# core_io.net
KiCad netlist of a schematic drawn in EAGLE
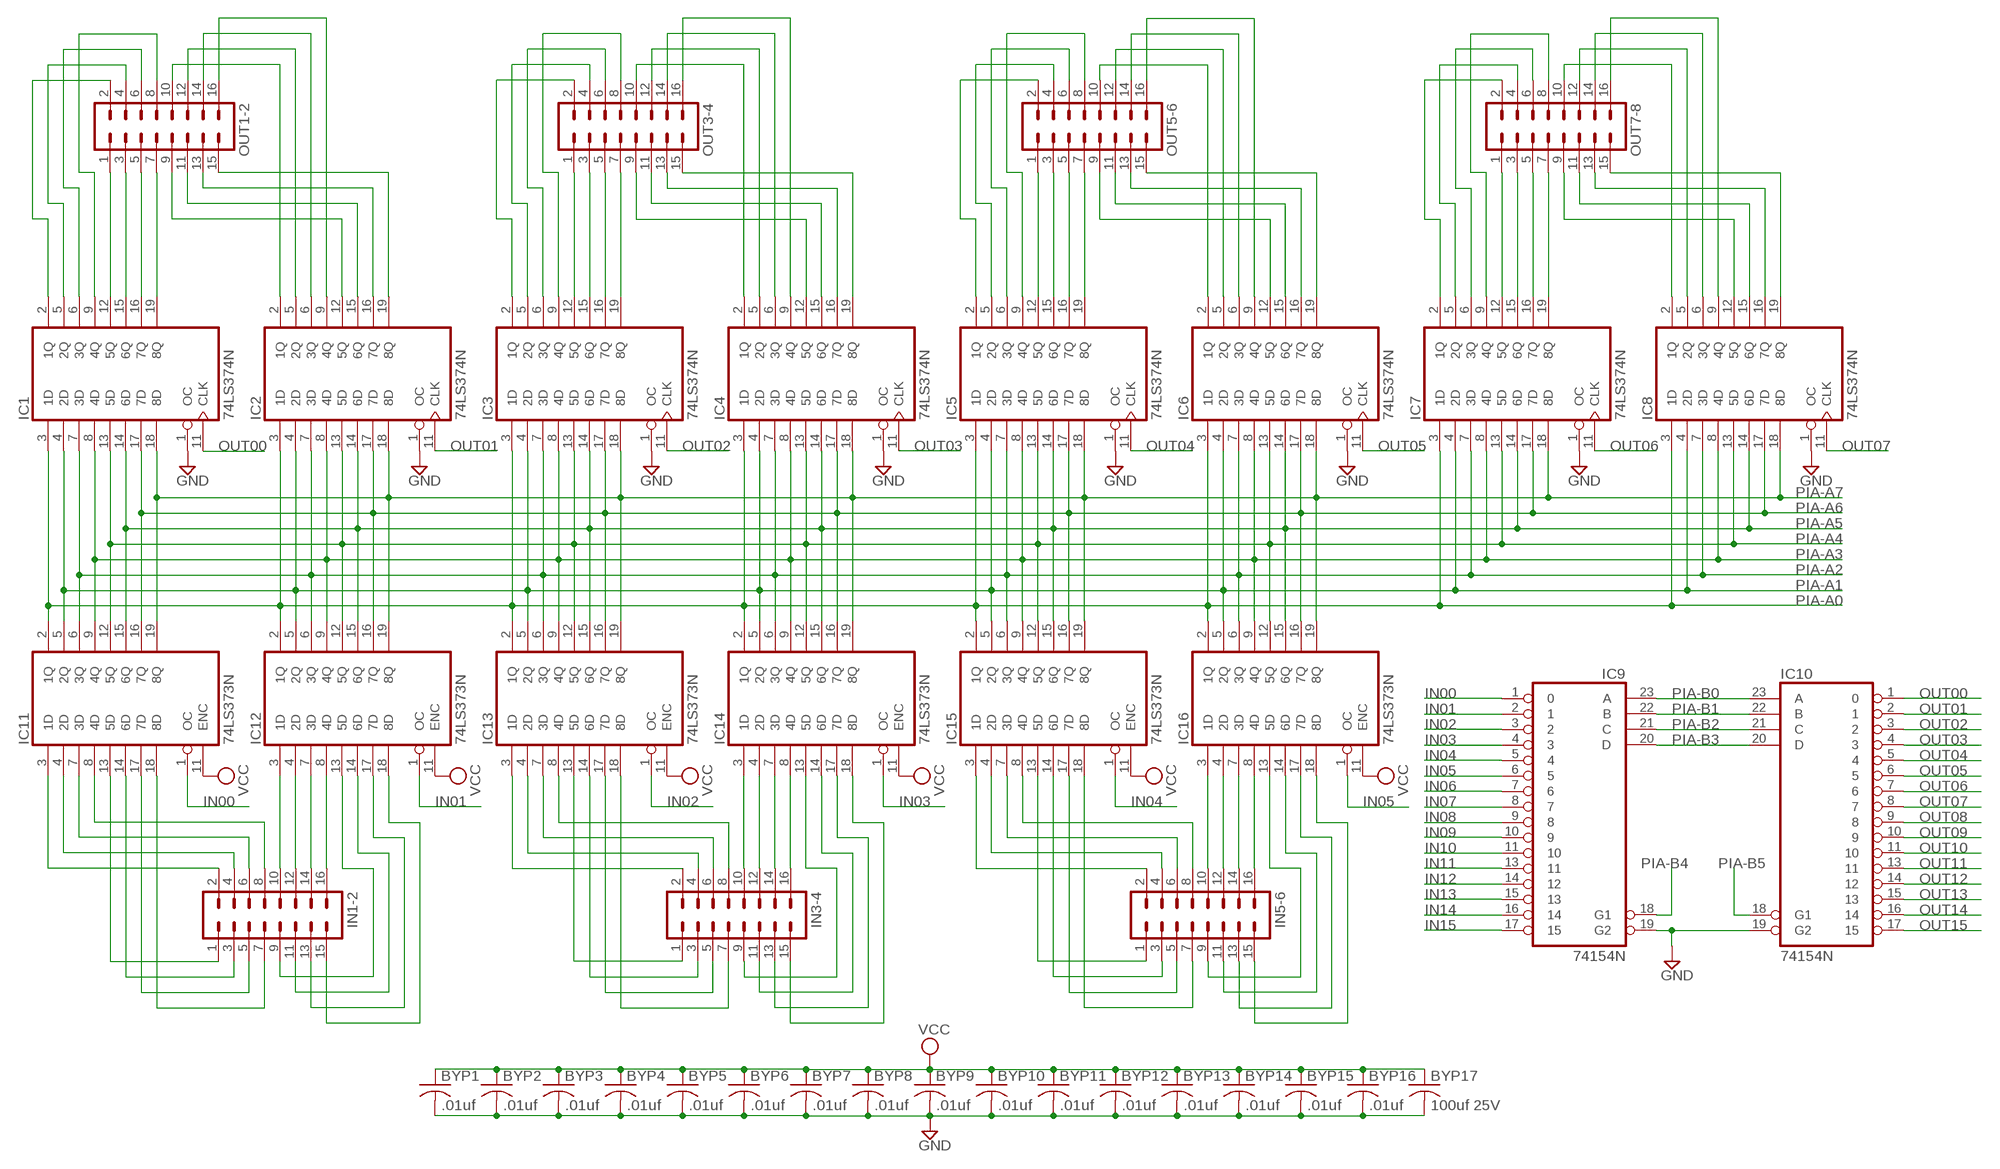
[diagram p0: schematic, sheet 1]
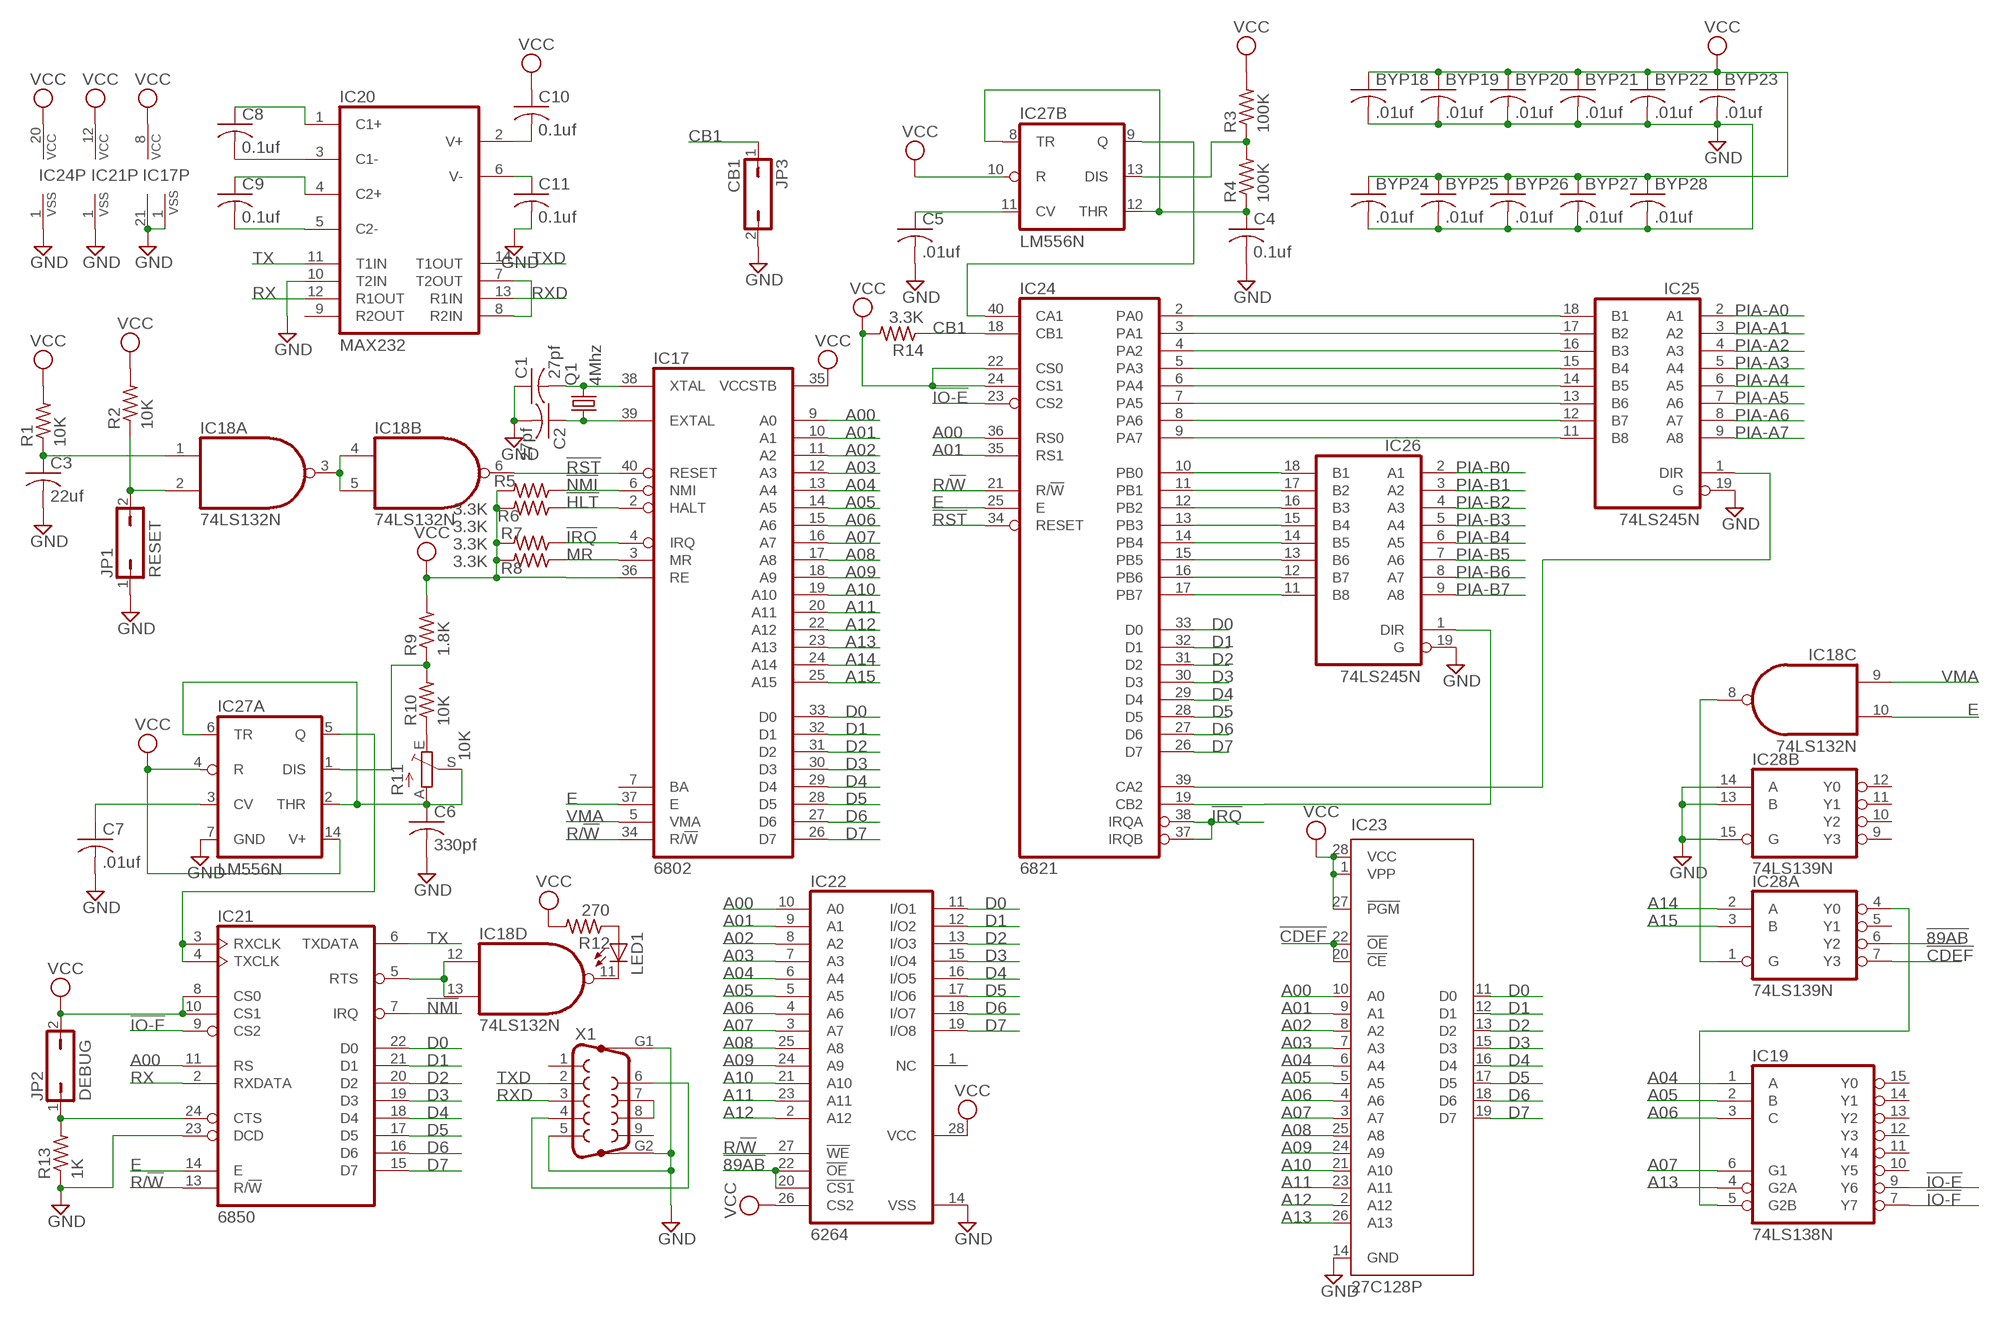
[diagram p1: schematic, sheet 2]
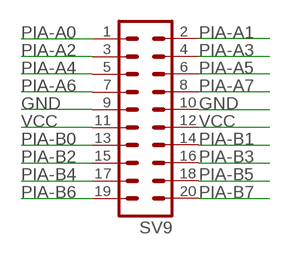
[diagram p2: schematic, sheet 3]

(export (version "E")
  (design (tool "Eeschema 10.0.6"))
  (components
    (comp (ref "SV9")
      (value "MA10-2")
      (footprint "eagle-import:MA10-2")
      (libsource (lib "eagle-import") (part "MA10-2"))
    )
    (comp (ref "BYP1")
      (value ".01uf")
      (footprint "eagle-import:C050-025X075")
      (libsource (lib "eagle-import") (part "C-US050-025X075"))
    )
    (comp (ref "BYP2")
      (value ".01uf")
      (footprint "eagle-import:C050-025X075")
      (libsource (lib "eagle-import") (part "C-US050-025X075"))
    )
    (comp (ref "BYP3")
      (value ".01uf")
      (footprint "eagle-import:C050-025X075")
      (libsource (lib "eagle-import") (part "C-US050-025X075"))
    )
    (comp (ref "BYP4")
      (value ".01uf")
      (footprint "eagle-import:C050-025X075")
      (libsource (lib "eagle-import") (part "C-US050-025X075"))
    )
    (comp (ref "BYP5")
      (value ".01uf")
      (footprint "eagle-import:C050-025X075")
      (libsource (lib "eagle-import") (part "C-US050-025X075"))
    )
    (comp (ref "BYP6")
      (value ".01uf")
      (footprint "eagle-import:C050-025X075")
      (libsource (lib "eagle-import") (part "C-US050-025X075"))
    )
    (comp (ref "BYP7")
      (value ".01uf")
      (footprint "eagle-import:C050-025X075")
      (libsource (lib "eagle-import") (part "C-US050-025X075"))
    )
    (comp (ref "BYP8")
      (value ".01uf")
      (footprint "eagle-import:C050-025X075")
      (libsource (lib "eagle-import") (part "C-US050-025X075"))
    )
    (comp (ref "BYP9")
      (value ".01uf")
      (footprint "eagle-import:C050-025X075")
      (libsource (lib "eagle-import") (part "C-US050-025X075"))
    )
    (comp (ref "BYP10")
      (value ".01uf")
      (footprint "eagle-import:C050-025X075")
      (libsource (lib "eagle-import") (part "C-US050-025X075"))
    )
    (comp (ref "BYP11")
      (value ".01uf")
      (footprint "eagle-import:C050-025X075")
      (libsource (lib "eagle-import") (part "C-US050-025X075"))
    )
    (comp (ref "BYP12")
      (value ".01uf")
      (footprint "eagle-import:C050-025X075")
      (libsource (lib "eagle-import") (part "C-US050-025X075"))
    )
    (comp (ref "BYP13")
      (value ".01uf")
      (footprint "eagle-import:C050-025X075")
      (libsource (lib "eagle-import") (part "C-US050-025X075"))
    )
    (comp (ref "BYP14")
      (value ".01uf")
      (footprint "eagle-import:C050-025X075")
      (libsource (lib "eagle-import") (part "C-US050-025X075"))
    )
    (comp (ref "BYP15")
      (value ".01uf")
      (footprint "eagle-import:C050-025X075")
      (libsource (lib "eagle-import") (part "C-US050-025X075"))
    )
    (comp (ref "BYP16")
      (value ".01uf")
      (footprint "eagle-import:C050-025X075")
      (libsource (lib "eagle-import") (part "C-US050-025X075"))
    )
    (comp (ref "BYP17")
      (value "100uf 25V")
      (footprint "eagle-import:C102-043X133")
      (libsource (lib "eagle-import") (part "C-US102-043X133"))
    )
    (comp (ref "IC1")
      (value "74LS374N")
      (footprint "eagle-import:DIL20")
      (libsource (lib "eagle-import") (part "74374NLS"))
    )
    (comp (ref "IC2")
      (value "74LS374N")
      (footprint "eagle-import:DIL20")
      (libsource (lib "eagle-import") (part "74374NLS"))
    )
    (comp (ref "IC3")
      (value "74LS374N")
      (footprint "eagle-import:DIL20")
      (libsource (lib "eagle-import") (part "74374NLS"))
    )
    (comp (ref "IC4")
      (value "74LS374N")
      (footprint "eagle-import:DIL20")
      (libsource (lib "eagle-import") (part "74374NLS"))
    )
    (comp (ref "IC5")
      (value "74LS374N")
      (footprint "eagle-import:DIL20")
      (libsource (lib "eagle-import") (part "74374NLS"))
    )
    (comp (ref "IC6")
      (value "74LS374N")
      (footprint "eagle-import:DIL20")
      (libsource (lib "eagle-import") (part "74374NLS"))
    )
    (comp (ref "IC7")
      (value "74LS374N")
      (footprint "eagle-import:DIL20")
      (libsource (lib "eagle-import") (part "74374NLS"))
    )
    (comp (ref "IC8")
      (value "74LS374N")
      (footprint "eagle-import:DIL20")
      (libsource (lib "eagle-import") (part "74374NLS"))
    )
    (comp (ref "IC9")
      (value "74154N")
      (footprint "eagle-import:DIL24-6")
      (libsource (lib "eagle-import") (part "74154N"))
    )
    (comp (ref "IC10")
      (value "74154N")
      (footprint "eagle-import:DIL24-6")
      (libsource (lib "eagle-import") (part "74154N"))
    )
    (comp (ref "IC11")
      (value "74LS373N")
      (footprint "eagle-import:DIL20")
      (libsource (lib "eagle-import") (part "74373NLS"))
    )
    (comp (ref "IC12")
      (value "74LS373N")
      (footprint "eagle-import:DIL20")
      (libsource (lib "eagle-import") (part "74373NLS"))
    )
    (comp (ref "IC13")
      (value "74LS373N")
      (footprint "eagle-import:DIL20")
      (libsource (lib "eagle-import") (part "74373NLS"))
    )
    (comp (ref "IC14")
      (value "74LS373N")
      (footprint "eagle-import:DIL20")
      (libsource (lib "eagle-import") (part "74373NLS"))
    )
    (comp (ref "IC15")
      (value "74LS373N")
      (footprint "eagle-import:DIL20")
      (libsource (lib "eagle-import") (part "74373NLS"))
    )
    (comp (ref "IC16")
      (value "74LS373N")
      (footprint "eagle-import:DIL20")
      (libsource (lib "eagle-import") (part "74373NLS"))
    )
    (comp (ref "IN1-2")
      (value "MA08-2")
      (footprint "eagle-import:MA08-2")
      (libsource (lib "eagle-import") (part "MA08-2"))
    )
    (comp (ref "IN3-4")
      (value "MA08-2")
      (footprint "eagle-import:MA08-2")
      (libsource (lib "eagle-import") (part "MA08-2"))
    )
    (comp (ref "IN5-6")
      (value "MA08-2")
      (footprint "eagle-import:MA08-2")
      (libsource (lib "eagle-import") (part "MA08-2"))
    )
    (comp (ref "OUT1-2")
      (value "MA08-2")
      (footprint "eagle-import:MA08-2")
      (libsource (lib "eagle-import") (part "MA08-2"))
    )
    (comp (ref "OUT3-4")
      (value "MA08-2")
      (footprint "eagle-import:MA08-2")
      (libsource (lib "eagle-import") (part "MA08-2"))
    )
    (comp (ref "OUT5-6")
      (value "MA08-2")
      (footprint "eagle-import:MA08-2")
      (libsource (lib "eagle-import") (part "MA08-2"))
    )
    (comp (ref "OUT7-8")
      (value "MA08-2")
      (footprint "eagle-import:MA08-2")
      (libsource (lib "eagle-import") (part "MA08-2"))
    )
    (comp (ref "BYP18")
      (value ".01uf")
      (footprint "eagle-import:C050-025X075")
      (libsource (lib "eagle-import") (part "C-US050-025X075"))
    )
    (comp (ref "BYP19")
      (value ".01uf")
      (footprint "eagle-import:C050-025X075")
      (libsource (lib "eagle-import") (part "C-US050-025X075"))
    )
    (comp (ref "BYP20")
      (value ".01uf")
      (footprint "eagle-import:C050-025X075")
      (libsource (lib "eagle-import") (part "C-US050-025X075"))
    )
    (comp (ref "BYP21")
      (value ".01uf")
      (footprint "eagle-import:C050-025X075")
      (libsource (lib "eagle-import") (part "C-US050-025X075"))
    )
    (comp (ref "BYP22")
      (value ".01uf")
      (footprint "eagle-import:C050-025X075")
      (libsource (lib "eagle-import") (part "C-US050-025X075"))
    )
    (comp (ref "BYP23")
      (value ".01uf")
      (footprint "eagle-import:C050-025X075")
      (libsource (lib "eagle-import") (part "C-US050-025X075"))
    )
    (comp (ref "BYP24")
      (value ".01uf")
      (footprint "eagle-import:C050-025X075")
      (libsource (lib "eagle-import") (part "C-US050-025X075"))
    )
    (comp (ref "BYP25")
      (value ".01uf")
      (footprint "eagle-import:C050-025X075")
      (libsource (lib "eagle-import") (part "C-US050-025X075"))
    )
    (comp (ref "BYP26")
      (value ".01uf")
      (footprint "eagle-import:C050-025X075")
      (libsource (lib "eagle-import") (part "C-US050-025X075"))
    )
    (comp (ref "BYP27")
      (value ".01uf")
      (footprint "eagle-import:C050-025X075")
      (libsource (lib "eagle-import") (part "C-US050-025X075"))
    )
    (comp (ref "BYP28")
      (value ".01uf")
      (footprint "eagle-import:C050-025X075")
      (libsource (lib "eagle-import") (part "C-US050-025X075"))
    )
    (comp (ref "C1")
      (value "27pf")
      (footprint "eagle-import:C050-025X075")
      (libsource (lib "eagle-import") (part "C-US050-025X075"))
    )
    (comp (ref "C2")
      (value "27pf")
      (footprint "eagle-import:C050-025X075")
      (libsource (lib "eagle-import") (part "C-US050-025X075"))
    )
    (comp (ref "C3")
      (value "22uf")
      (footprint "eagle-import:C102-043X133")
      (libsource (lib "eagle-import") (part "C-US102-043X133"))
    )
    (comp (ref "C4")
      (value "0.1uf")
      (footprint "eagle-import:C050-025X075")
      (libsource (lib "eagle-import") (part "C-US050-025X075"))
    )
    (comp (ref "C5")
      (value ".01uf")
      (footprint "eagle-import:C050-025X075")
      (libsource (lib "eagle-import") (part "C-US050-025X075"))
    )
    (comp (ref "C6")
      (value "330pf")
      (footprint "eagle-import:C050-025X075")
      (libsource (lib "eagle-import") (part "C-US050-025X075"))
    )
    (comp (ref "C7")
      (value ".01uf")
      (footprint "eagle-import:C050-025X075")
      (libsource (lib "eagle-import") (part "C-US050-025X075"))
    )
    (comp (ref "C8")
      (value "0.1uf")
      (footprint "eagle-import:C050-025X075")
      (libsource (lib "eagle-import") (part "C-US050-025X075"))
    )
    (comp (ref "C9")
      (value "0.1uf")
      (footprint "eagle-import:C050-025X075")
      (libsource (lib "eagle-import") (part "C-US050-025X075"))
    )
    (comp (ref "C10")
      (value "0.1uf")
      (footprint "eagle-import:C050-025X075")
      (libsource (lib "eagle-import") (part "C-US050-025X075"))
    )
    (comp (ref "C11")
      (value "0.1uf")
      (footprint "eagle-import:C050-025X075")
      (libsource (lib "eagle-import") (part "C-US050-025X075"))
    )
    (comp (ref "IC17")
      (value "6802")
      (footprint "eagle-import:DIL40")
      (libsource (lib "eagle-import") (part "6802"))
    )
    (comp (ref "IC18")
      (value "74LS132N")
      (footprint "eagle-import:DIL14")
      (libsource (lib "eagle-import") (part "7400NLS"))
    )
    (comp (ref "IC19")
      (value "74LS138N")
      (footprint "eagle-import:DIL16")
      (libsource (lib "eagle-import") (part "74138NLS"))
    )
    (comp (ref "IC20")
      (value "MAX232")
      (footprint "eagle-import:DIL16")
      (fields (field (name "MF") "MAXIM") (field (name "MPN") "MAX232ACPE+"))
      (libsource (lib "eagle-import") (part "MAX232"))
    )
    (comp (ref "IC21")
      (value "6850")
      (footprint "eagle-import:DIL24")
      (fields (field (name "MF") "NTE ELECTRONICS") (field (name "MPN") "NTE6850"))
      (libsource (lib "eagle-import") (part "6850"))
    )
    (comp (ref "IC22")
      (value "6264")
      (footprint "eagle-import:DIL28-6")
      (libsource (lib "eagle-import") (part "6264A"))
    )
    (comp (ref "IC23")
      (value "27C128P")
      (footprint "eagle-import:DIL28-6")
      (libsource (lib "eagle-import") (part "27128PC"))
    )
    (comp (ref "IC24")
      (value "6821")
      (footprint "eagle-import:DIL40")
      (fields (field (name "MF") "NTE ELECTRONICS") (field (name "MPN") "NTE6821"))
      (libsource (lib "eagle-import") (part "6821"))
    )
    (comp (ref "IC25")
      (value "74LS245N")
      (footprint "eagle-import:DIL20")
      (libsource (lib "eagle-import") (part "74245NLS"))
    )
    (comp (ref "IC26")
      (value "74LS245N")
      (footprint "eagle-import:DIL20")
      (libsource (lib "eagle-import") (part "74245NLS"))
    )
    (comp (ref "IC27")
      (value "LM556N")
      (footprint "eagle-import:DIL14")
      (libsource (lib "eagle-import") (part "556NLM"))
    )
    (comp (ref "IC28")
      (value "74LS139N")
      (footprint "eagle-import:DIL16")
      (libsource (lib "eagle-import") (part "74139NLS"))
    )
    (comp (ref "JP1")
      (value "RESET")
      (footprint "eagle-import:JP1")
      (libsource (lib "eagle-import") (part "JP1Q"))
    )
    (comp (ref "JP2")
      (value "DEBUG")
      (footprint "eagle-import:JP1")
      (libsource (lib "eagle-import") (part "JP1Q"))
    )
    (comp (ref "JP3")
      (value "CB1")
      (footprint "eagle-import:JP1")
      (libsource (lib "eagle-import") (part "JP1Q"))
    )
    (comp (ref "LED1")
      (value "LED3MM")
      (footprint "eagle-import:LED3MM")
      (libsource (lib "eagle-import") (part "LED3MM"))
    )
    (comp (ref "Q1")
      (value "4Mhz")
      (footprint "eagle-import:HC18U-V")
      (libsource (lib "eagle-import") (part "CRYSTALHC18U-V"))
    )
    (comp (ref "R1")
      (value "10K")
      (footprint "eagle-import:0207_7")
      (libsource (lib "eagle-import") (part "R-US_0207/7"))
    )
    (comp (ref "R2")
      (value "10K")
      (footprint "eagle-import:0207_7")
      (libsource (lib "eagle-import") (part "R-US_0207/7"))
    )
    (comp (ref "R3")
      (value "100K")
      (footprint "eagle-import:0207_7")
      (libsource (lib "eagle-import") (part "R-US_0207/7"))
    )
    (comp (ref "R4")
      (value "100K")
      (footprint "eagle-import:0207_7")
      (libsource (lib "eagle-import") (part "R-US_0207/7"))
    )
    (comp (ref "R5")
      (value "3.3K")
      (footprint "eagle-import:0207_7")
      (libsource (lib "eagle-import") (part "R-US_0207/7"))
    )
    (comp (ref "R6")
      (value "3.3K")
      (footprint "eagle-import:0207_7")
      (libsource (lib "eagle-import") (part "R-US_0207/7"))
    )
    (comp (ref "R7")
      (value "3.3K")
      (footprint "eagle-import:0207_7")
      (libsource (lib "eagle-import") (part "R-US_0207/7"))
    )
    (comp (ref "R8")
      (value "3.3K")
      (footprint "eagle-import:0207_7")
      (libsource (lib "eagle-import") (part "R-US_0207/7"))
    )
    (comp (ref "R9")
      (value "1.8K")
      (footprint "eagle-import:0207_7")
      (libsource (lib "eagle-import") (part "R-US_0207/7"))
    )
    (comp (ref "R10")
      (value "10K")
      (footprint "eagle-import:0207_7")
      (libsource (lib "eagle-import") (part "R-US_0207/7"))
    )
    (comp (ref "R11")
      (value "10K")
      (footprint "eagle-import:SP19L")
      (libsource (lib "eagle-import") (part "TRIM_EU-B90P"))
    )
    (comp (ref "R12")
      (value "270")
      (footprint "eagle-import:0207_7")
      (libsource (lib "eagle-import") (part "R-US_0207/7"))
    )
    (comp (ref "R13")
      (value "1K")
      (footprint "eagle-import:0207_7")
      (libsource (lib "eagle-import") (part "R-US_0207/7"))
    )
    (comp (ref "R14")
      (value "3.3K")
      (footprint "eagle-import:0207_7")
      (libsource (lib "eagle-import") (part "R-US_0207/7"))
    )
    (comp (ref "X1")
      (value "F09HP")
      (footprint "eagle-import:F09HP")
      (libsource (lib "eagle-import") (part "F09HP"))
    )
  )
  (nets
    (net (code "1") (name "A00") (class "Default")
      (node (ref "IC17") (pin "9") (pinfunction "A0_9") (pintype "output"))
      (node (ref "IC21") (pin "11") (pinfunction "RS_11") (pintype "input"))
      (node (ref "IC22") (pin "10") (pinfunction "A0_10") (pintype "input"))
      (node (ref "IC23") (pin "10") (pinfunction "A0_10") (pintype "input"))
      (node (ref "IC24") (pin "36") (pinfunction "RS0_36") (pintype "input"))
    )
    (net (code "2") (name "A01") (class "Default")
      (node (ref "IC17") (pin "10") (pinfunction "A1_10") (pintype "output"))
      (node (ref "IC22") (pin "9") (pinfunction "A1_9") (pintype "input"))
      (node (ref "IC23") (pin "9") (pinfunction "A1_9") (pintype "input"))
      (node (ref "IC24") (pin "35") (pinfunction "RS1_35") (pintype "input"))
    )
    (net (code "3") (name "A02") (class "Default")
      (node (ref "IC17") (pin "11") (pinfunction "A2_11") (pintype "output"))
      (node (ref "IC22") (pin "8") (pinfunction "A2_8") (pintype "input"))
      (node (ref "IC23") (pin "8") (pinfunction "A2_8") (pintype "input"))
    )
    (net (code "4") (name "A03") (class "Default")
      (node (ref "IC17") (pin "12") (pinfunction "A3_12") (pintype "output"))
      (node (ref "IC22") (pin "7") (pinfunction "A3_7") (pintype "input"))
      (node (ref "IC23") (pin "7") (pinfunction "A3_7") (pintype "input"))
    )
    (net (code "5") (name "A04") (class "Default")
      (node (ref "IC17") (pin "13") (pinfunction "A4_13") (pintype "output"))
      (node (ref "IC19") (pin "1") (pinfunction "A_1") (pintype "input"))
      (node (ref "IC22") (pin "6") (pinfunction "A4_6") (pintype "input"))
      (node (ref "IC23") (pin "6") (pinfunction "A4_6") (pintype "input"))
    )
    (net (code "6") (name "A05") (class "Default")
      (node (ref "IC17") (pin "14") (pinfunction "A5_14") (pintype "output"))
      (node (ref "IC19") (pin "2") (pinfunction "B_2") (pintype "input"))
      (node (ref "IC22") (pin "5") (pinfunction "A5_5") (pintype "input"))
      (node (ref "IC23") (pin "5") (pinfunction "A5_5") (pintype "input"))
    )
    (net (code "7") (name "A06") (class "Default")
      (node (ref "IC17") (pin "15") (pinfunction "A6_15") (pintype "output"))
      (node (ref "IC19") (pin "3") (pinfunction "C_3") (pintype "input"))
      (node (ref "IC22") (pin "4") (pinfunction "A6_4") (pintype "input"))
      (node (ref "IC23") (pin "4") (pinfunction "A6_4") (pintype "input"))
    )
    (net (code "8") (name "A07") (class "Default")
      (node (ref "IC17") (pin "16") (pinfunction "A7_16") (pintype "output"))
      (node (ref "IC19") (pin "6") (pinfunction "G1_6") (pintype "input"))
      (node (ref "IC22") (pin "3") (pinfunction "A7_3") (pintype "input"))
      (node (ref "IC23") (pin "3") (pinfunction "A7_3") (pintype "input"))
    )
    (net (code "9") (name "A08") (class "Default")
      (node (ref "IC17") (pin "17") (pinfunction "A8_17") (pintype "output"))
      (node (ref "IC22") (pin "25") (pinfunction "A8_25") (pintype "input"))
      (node (ref "IC23") (pin "25") (pinfunction "A8_25") (pintype "input"))
    )
    (net (code "10") (name "A09") (class "Default")
      (node (ref "IC17") (pin "18") (pinfunction "A9_18") (pintype "output"))
      (node (ref "IC22") (pin "24") (pinfunction "A9_24") (pintype "input"))
      (node (ref "IC23") (pin "24") (pinfunction "A9_24") (pintype "input"))
    )
    (net (code "11") (name "A10") (class "Default")
      (node (ref "IC17") (pin "19") (pinfunction "A10_19") (pintype "output"))
      (node (ref "IC22") (pin "21") (pinfunction "A10_21") (pintype "input"))
      (node (ref "IC23") (pin "21") (pinfunction "A10_21") (pintype "input"))
    )
    (net (code "12") (name "A11") (class "Default")
      (node (ref "IC17") (pin "20") (pinfunction "A11_20") (pintype "output"))
      (node (ref "IC22") (pin "23") (pinfunction "A11_23") (pintype "input"))
      (node (ref "IC23") (pin "23") (pinfunction "A11_23") (pintype "input"))
    )
    (net (code "13") (name "A12") (class "Default")
      (node (ref "IC17") (pin "22") (pinfunction "A12_22") (pintype "output"))
      (node (ref "IC22") (pin "2") (pinfunction "A12_2") (pintype "input"))
      (node (ref "IC23") (pin "2") (pinfunction "A12_2") (pintype "input"))
    )
    (net (code "14") (name "A13") (class "Default")
      (node (ref "IC17") (pin "23") (pinfunction "A13_23") (pintype "output"))
      (node (ref "IC19") (pin "4") (pinfunction "G2A_4") (pintype "input"))
      (node (ref "IC23") (pin "26") (pinfunction "A13_26") (pintype "input"))
    )
    (net (code "15") (name "A14") (class "Default")
      (node (ref "IC17") (pin "24") (pinfunction "A14_24") (pintype "output"))
      (node (ref "IC28") (pin "2") (pinfunction "A_2") (pintype "input"))
    )
    (net (code "16") (name "A15") (class "Default")
      (node (ref "IC17") (pin "25") (pinfunction "A15_25") (pintype "output"))
      (node (ref "IC28") (pin "3") (pinfunction "B_3") (pintype "input"))
    )
    (net (code "17") (name "CB1") (class "Default")
      (node (ref "IC24") (pin "18") (pinfunction "CB1_18") (pintype "input"))
      (node (ref "JP3") (pin "1") (pinfunction "1_1") (pintype "passive"))
      (node (ref "R14") (pin "1") (pinfunction "1_1") (pintype "passive"))
    )
    (net (code "18") (name "D0") (class "Default")
      (node (ref "IC17") (pin "33") (pinfunction "D0_33") (pintype "bidirectional"))
      (node (ref "IC21") (pin "22") (pinfunction "D0_22") (pintype "bidirectional"))
      (node (ref "IC22") (pin "11") (pinfunction "I/O1_11") (pintype "bidirectional"))
      (node (ref "IC23") (pin "11") (pinfunction "D0_11") (pintype "tri_state"))
      (node (ref "IC24") (pin "33") (pinfunction "D0_33") (pintype "bidirectional"))
    )
    (net (code "19") (name "D1") (class "Default")
      (node (ref "IC17") (pin "32") (pinfunction "D1_32") (pintype "bidirectional"))
      (node (ref "IC21") (pin "21") (pinfunction "D1_21") (pintype "bidirectional"))
      (node (ref "IC22") (pin "12") (pinfunction "I/O2_12") (pintype "bidirectional"))
      (node (ref "IC23") (pin "12") (pinfunction "D1_12") (pintype "tri_state"))
      (node (ref "IC24") (pin "32") (pinfunction "D1_32") (pintype "bidirectional"))
    )
    (net (code "20") (name "D2") (class "Default")
      (node (ref "IC17") (pin "31") (pinfunction "D2_31") (pintype "bidirectional"))
      (node (ref "IC21") (pin "20") (pinfunction "D2_20") (pintype "bidirectional"))
      (node (ref "IC22") (pin "13") (pinfunction "I/O3_13") (pintype "bidirectional"))
      (node (ref "IC23") (pin "13") (pinfunction "D2_13") (pintype "tri_state"))
      (node (ref "IC24") (pin "31") (pinfunction "D2_31") (pintype "bidirectional"))
    )
    (net (code "21") (name "D3") (class "Default")
      (node (ref "IC17") (pin "30") (pinfunction "D3_30") (pintype "bidirectional"))
      (node (ref "IC21") (pin "19") (pinfunction "D3_19") (pintype "bidirectional"))
      (node (ref "IC22") (pin "15") (pinfunction "I/O4_15") (pintype "bidirectional"))
      (node (ref "IC23") (pin "15") (pinfunction "D3_15") (pintype "tri_state"))
      (node (ref "IC24") (pin "30") (pinfunction "D3_30") (pintype "bidirectional"))
    )
    (net (code "22") (name "D4") (class "Default")
      (node (ref "IC17") (pin "29") (pinfunction "D4_29") (pintype "bidirectional"))
      (node (ref "IC21") (pin "18") (pinfunction "D4_18") (pintype "bidirectional"))
      (node (ref "IC22") (pin "16") (pinfunction "I/O5_16") (pintype "bidirectional"))
      (node (ref "IC23") (pin "16") (pinfunction "D4_16") (pintype "tri_state"))
      (node (ref "IC24") (pin "29") (pinfunction "D4_29") (pintype "bidirectional"))
    )
    (net (code "23") (name "D5") (class "Default")
      (node (ref "IC17") (pin "28") (pinfunction "D5_28") (pintype "bidirectional"))
      (node (ref "IC21") (pin "17") (pinfunction "D5_17") (pintype "bidirectional"))
      (node (ref "IC22") (pin "17") (pinfunction "I/O6_17") (pintype "bidirectional"))
      (node (ref "IC23") (pin "17") (pinfunction "D5_17") (pintype "tri_state"))
      (node (ref "IC24") (pin "28") (pinfunction "D5_28") (pintype "bidirectional"))
    )
    (net (code "24") (name "D6") (class "Default")
      (node (ref "IC17") (pin "27") (pinfunction "D6_27") (pintype "bidirectional"))
      (node (ref "IC21") (pin "16") (pinfunction "D6_16") (pintype "bidirectional"))
      (node (ref "IC22") (pin "18") (pinfunction "I/O7_18") (pintype "bidirectional"))
      (node (ref "IC23") (pin "18") (pinfunction "D6_18") (pintype "tri_state"))
      (node (ref "IC24") (pin "27") (pinfunction "D6_27") (pintype "bidirectional"))
    )
    (net (code "25") (name "D7") (class "Default")
      (node (ref "IC17") (pin "26") (pinfunction "D7_26") (pintype "bidirectional"))
      (node (ref "IC21") (pin "15") (pinfunction "D7_15") (pintype "bidirectional"))
      (node (ref "IC22") (pin "19") (pinfunction "I/O8_19") (pintype "bidirectional"))
      (node (ref "IC23") (pin "19") (pinfunction "D7_19") (pintype "tri_state"))
      (node (ref "IC24") (pin "26") (pinfunction "D7_26") (pintype "bidirectional"))
    )
    (net (code "26") (name "E") (class "Default")
      (node (ref "IC17") (pin "37") (pinfunction "E_37") (pintype "output"))
      (node (ref "IC18") (pin "10") (pinfunction "I1_10") (pintype "input"))
      (node (ref "IC21") (pin "14") (pinfunction "E_14") (pintype "input"))
      (node (ref "IC24") (pin "25") (pinfunction "E_25") (pintype "input"))
    )
    (net (code "27") (name "GND") (class "Default")
      (node (ref "BYP1") (pin "2") (pinfunction "2_2") (pintype "passive"))
      (node (ref "BYP10") (pin "2") (pinfunction "2_2") (pintype "passive"))
      (node (ref "BYP11") (pin "2") (pinfunction "2_2") (pintype "passive"))
      (node (ref "BYP12") (pin "2") (pinfunction "2_2") (pintype "passive"))
      (node (ref "BYP13") (pin "2") (pinfunction "2_2") (pintype "passive"))
      (node (ref "BYP14") (pin "2") (pinfunction "2_2") (pintype "passive"))
      (node (ref "BYP15") (pin "2") (pinfunction "2_2") (pintype "passive"))
      (node (ref "BYP16") (pin "2") (pinfunction "2_2") (pintype "passive"))
      (node (ref "BYP17") (pin "2") (pinfunction "2_2") (pintype "passive"))
      (node (ref "BYP18") (pin "2") (pinfunction "2_2") (pintype "passive"))
      (node (ref "BYP19") (pin "2") (pinfunction "2_2") (pintype "passive"))
      (node (ref "BYP2") (pin "2") (pinfunction "2_2") (pintype "passive"))
      (node (ref "BYP20") (pin "2") (pinfunction "2_2") (pintype "passive"))
      (node (ref "BYP21") (pin "2") (pinfunction "2_2") (pintype "passive"))
      (node (ref "BYP22") (pin "2") (pinfunction "2_2") (pintype "passive"))
      (node (ref "BYP23") (pin "2") (pinfunction "2_2") (pintype "passive"))
      (node (ref "BYP24") (pin "2") (pinfunction "2_2") (pintype "passive"))
      (node (ref "BYP25") (pin "2") (pinfunction "2_2") (pintype "passive"))
      (node (ref "BYP26") (pin "2") (pinfunction "2_2") (pintype "passive"))
      (node (ref "BYP27") (pin "2") (pinfunction "2_2") (pintype "passive"))
      (node (ref "BYP28") (pin "2") (pinfunction "2_2") (pintype "passive"))
      (node (ref "BYP3") (pin "2") (pinfunction "2_2") (pintype "passive"))
      (node (ref "BYP4") (pin "2") (pinfunction "2_2") (pintype "passive"))
      (node (ref "BYP5") (pin "2") (pinfunction "2_2") (pintype "passive"))
      (node (ref "BYP6") (pin "2") (pinfunction "2_2") (pintype "passive"))
      (node (ref "BYP7") (pin "2") (pinfunction "2_2") (pintype "passive"))
      (node (ref "BYP8") (pin "2") (pinfunction "2_2") (pintype "passive"))
      (node (ref "BYP9") (pin "2") (pinfunction "2_2") (pintype "passive"))
      (node (ref "C1") (pin "1") (pinfunction "1_1") (pintype "passive"))
      (node (ref "C11") (pin "2") (pinfunction "2_2") (pintype "passive"))
      (node (ref "C2") (pin "2") (pinfunction "2_2") (pintype "passive"))
      (node (ref "C3") (pin "2") (pinfunction "2_2") (pintype "passive"))
      (node (ref "C4") (pin "2") (pinfunction "2_2") (pintype "passive"))
      (node (ref "C5") (pin "2") (pinfunction "2_2") (pintype "passive"))
      (node (ref "C6") (pin "2") (pinfunction "2_2") (pintype "passive"))
      (node (ref "C7") (pin "2") (pinfunction "2_2") (pintype "passive"))
      (node (ref "IC1") (pin "1") (pinfunction "OC_1") (pintype "input"))
      (node (ref "IC10") (pin "19") (pinfunction "G2_19") (pintype "input"))
      (node (ref "IC17") (pin "1") (pinfunction "VSS_1") (pintype "power_in"))
      (node (ref "IC17") (pin "21") (pinfunction "VSS_21") (pintype "power_in"))
      (node (ref "IC2") (pin "1") (pinfunction "OC_1") (pintype "input"))
      (node (ref "IC20") (pin "10") (pinfunction "T2IN_10") (pintype "input"))
      (node (ref "IC21") (pin "1") (pinfunction "VSS_1") (pintype "power_in"))
      (node (ref "IC21") (pin "23") (pinfunction "DCD_23") (pintype "input"))
      (node (ref "IC22") (pin "14") (pinfunction "VSS_14") (pintype "power_in"))
      (node (ref "IC23") (pin "14") (pinfunction "GND_14") (pintype "power_in"))
      (node (ref "IC24") (pin "1") (pinfunction "VSS_1") (pintype "power_in"))
      (node (ref "IC25") (pin "19") (pinfunction "G_19") (pintype "input"))
      (node (ref "IC26") (pin "19") (pinfunction "G_19") (pintype "input"))
      (node (ref "IC27") (pin "7") (pinfunction "GND_7") (pintype "power_in"))
      (node (ref "IC28") (pin "13") (pinfunction "B_13") (pintype "input"))
      (node (ref "IC28") (pin "14") (pinfunction "A_14") (pintype "input"))
      (node (ref "IC28") (pin "15") (pinfunction "G_15") (pintype "input"))
      (node (ref "IC3") (pin "1") (pinfunction "OC_1") (pintype "input"))
      (node (ref "IC4") (pin "1") (pinfunction "OC_1") (pintype "input"))
      (node (ref "IC5") (pin "1") (pinfunction "OC_1") (pintype "input"))
      (node (ref "IC6") (pin "1") (pinfunction "OC_1") (pintype "input"))
      (node (ref "IC7") (pin "1") (pinfunction "OC_1") (pintype "input"))
      (node (ref "IC8") (pin "1") (pinfunction "OC_1") (pintype "input"))
      (node (ref "IC9") (pin "19") (pinfunction "G2_19") (pintype "input"))
      (node (ref "JP1") (pin "1") (pinfunction "1_1") (pintype "passive"))
      (node (ref "JP3") (pin "2") (pinfunction "2_2") (pintype "passive"))
      (node (ref "R13") (pin "1") (pinfunction "1_1") (pintype "passive"))
      (node (ref "SV9") (pin "10") (pinfunction "10_10") (pintype "passive"))
      (node (ref "SV9") (pin "9") (pinfunction "9_9") (pintype "passive"))
      (node (ref "X1") (pin "5") (pinfunction "5_5") (pintype "passive"))
      (node (ref "X1") (pin "G1") (pinfunction "G1_G1") (pintype "passive"))
      (node (ref "X1") (pin "G2") (pinfunction "G2_G2") (pintype "passive"))
    )
    (net (code "28") (name "IN00") (class "Default")
      (node (ref "IC11") (pin "1") (pinfunction "OC_1") (pintype "input"))
      (node (ref "IC9") (pin "1") (pinfunction "0_1") (pintype "output"))
    )
    (net (code "29") (name "IN01") (class "Default")
      (node (ref "IC12") (pin "1") (pinfunction "OC_1") (pintype "input"))
      (node (ref "IC9") (pin "2") (pinfunction "1_2") (pintype "output"))
    )
    (net (code "30") (name "IN02") (class "Default")
      (node (ref "IC13") (pin "1") (pinfunction "OC_1") (pintype "input"))
      (node (ref "IC9") (pin "3") (pinfunction "2_3") (pintype "output"))
    )
    (net (code "31") (name "IN03") (class "Default")
      (node (ref "IC14") (pin "1") (pinfunction "OC_1") (pintype "input"))
      (node (ref "IC9") (pin "4") (pinfunction "3_4") (pintype "output"))
    )
    (net (code "32") (name "IN04") (class "Default")
      (node (ref "IC15") (pin "1") (pinfunction "OC_1") (pintype "input"))
      (node (ref "IC9") (pin "5") (pinfunction "4_5") (pintype "output"))
    )
    (net (code "33") (name "IN05") (class "Default")
      (node (ref "IC16") (pin "1") (pinfunction "OC_1") (pintype "input"))
      (node (ref "IC9") (pin "6") (pinfunction "5_6") (pintype "output"))
    )
    (net (code "34") (name "IN06") (class "Default")
      (node (ref "IC9") (pin "7") (pinfunction "6_7") (pintype "output"))
    )
    (net (code "35") (name "IN07") (class "Default")
      (node (ref "IC9") (pin "8") (pinfunction "7_8") (pintype "output"))
    )
    (net (code "36") (name "IN08") (class "Default")
      (node (ref "IC9") (pin "9") (pinfunction "8_9") (pintype "output"))
    )
    (net (code "37") (name "IN09") (class "Default")
      (node (ref "IC9") (pin "10") (pinfunction "9_10") (pintype "output"))
    )
    (net (code "38") (name "IN10") (class "Default")
      (node (ref "IC9") (pin "11") (pinfunction "10_11") (pintype "output"))
    )
    (net (code "39") (name "IN11") (class "Default")
      (node (ref "IC9") (pin "13") (pinfunction "11_13") (pintype "output"))
    )
    (net (code "40") (name "IN12") (class "Default")
      (node (ref "IC9") (pin "14") (pinfunction "12_14") (pintype "output"))
    )
    (net (code "41") (name "IN13") (class "Default")
      (node (ref "IC9") (pin "15") (pinfunction "13_15") (pintype "output"))
    )
    (net (code "42") (name "IN14") (class "Default")
      (node (ref "IC9") (pin "16") (pinfunction "14_16") (pintype "output"))
    )
    (net (code "43") (name "IN15") (class "Default")
      (node (ref "IC9") (pin "17") (pinfunction "15_17") (pintype "output"))
    )
    (net (code "44") (name "MR") (class "Default")
      (node (ref "IC17") (pin "3") (pinfunction "MR_3") (pintype "input"))
      (node (ref "R8") (pin "1") (pinfunction "1_1") (pintype "passive"))
    )
    (net (code "45") (name "Net-(IC1A-1Q)") (class "Default")
      (node (ref "IC1") (pin "2") (pinfunction "1Q_2") (pintype "tri_state"))
      (node (ref "OUT1-2") (pin "2") (pinfunction "2_2") (pintype "passive"))
    )
    (net (code "46") (name "Net-(IC1A-2Q)") (class "Default")
      (node (ref "IC1") (pin "5") (pinfunction "2Q_5") (pintype "tri_state"))
      (node (ref "OUT1-2") (pin "4") (pinfunction "4_4") (pintype "passive"))
    )
    (net (code "47") (name "Net-(IC1A-3Q)") (class "Default")
      (node (ref "IC1") (pin "6") (pinfunction "3Q_6") (pintype "tri_state"))
      (node (ref "OUT1-2") (pin "6") (pinfunction "6_6") (pintype "passive"))
    )
    (net (code "48") (name "Net-(IC1A-4Q)") (class "Default")
      (node (ref "IC1") (pin "9") (pinfunction "4Q_9") (pintype "tri_state"))
      (node (ref "OUT1-2") (pin "8") (pinfunction "8_8") (pintype "passive"))
    )
    (net (code "49") (name "Net-(IC1A-5Q)") (class "Default")
      (node (ref "IC1") (pin "12") (pinfunction "5Q_12") (pintype "tri_state"))
      (node (ref "OUT1-2") (pin "1") (pinfunction "1_1") (pintype "passive"))
    )
    (net (code "50") (name "Net-(IC1A-6Q)") (class "Default")
      (node (ref "IC1") (pin "15") (pinfunction "6Q_15") (pintype "tri_state"))
      (node (ref "OUT1-2") (pin "3") (pinfunction "3_3") (pintype "passive"))
    )
    (net (code "51") (name "Net-(IC1A-7Q)") (class "Default")
      (node (ref "IC1") (pin "16") (pinfunction "7Q_16") (pintype "tri_state"))
      (node (ref "OUT1-2") (pin "5") (pinfunction "5_5") (pintype "passive"))
    )
    (net (code "52") (name "Net-(IC1A-8Q)") (class "Default")
      (node (ref "IC1") (pin "19") (pinfunction "8Q_19") (pintype "tri_state"))
      (node (ref "OUT1-2") (pin "7") (pinfunction "7_7") (pintype "passive"))
    )
    (net (code "53") (name "Net-(IC2A-1Q)") (class "Default")
      (node (ref "IC2") (pin "2") (pinfunction "1Q_2") (pintype "tri_state"))
      (node (ref "OUT1-2") (pin "10") (pinfunction "10_10") (pintype "passive"))
    )
    (net (code "54") (name "Net-(IC2A-2Q)") (class "Default")
      (node (ref "IC2") (pin "5") (pinfunction "2Q_5") (pintype "tri_state"))
      (node (ref "OUT1-2") (pin "12") (pinfunction "12_12") (pintype "passive"))
    )
    (net (code "55") (name "Net-(IC2A-3Q)") (class "Default")
      (node (ref "IC2") (pin "6") (pinfunction "3Q_6") (pintype "tri_state"))
      (node (ref "OUT1-2") (pin "14") (pinfunction "14_14") (pintype "passive"))
    )
    (net (code "56") (name "Net-(IC2A-4Q)") (class "Default")
      (node (ref "IC2") (pin "9") (pinfunction "4Q_9") (pintype "tri_state"))
      (node (ref "OUT1-2") (pin "16") (pinfunction "16_16") (pintype "passive"))
    )
    (net (code "57") (name "Net-(IC2A-5Q)") (class "Default")
      (node (ref "IC2") (pin "12") (pinfunction "5Q_12") (pintype "tri_state"))
      (node (ref "OUT1-2") (pin "9") (pinfunction "9_9") (pintype "passive"))
    )
    (net (code "58") (name "Net-(IC2A-6Q)") (class "Default")
      (node (ref "IC2") (pin "15") (pinfunction "6Q_15") (pintype "tri_state"))
      (node (ref "OUT1-2") (pin "11") (pinfunction "11_11") (pintype "passive"))
    )
    (net (code "59") (name "Net-(IC2A-7Q)") (class "Default")
      (node (ref "IC2") (pin "16") (pinfunction "7Q_16") (pintype "tri_state"))
      (node (ref "OUT1-2") (pin "13") (pinfunction "13_13") (pintype "passive"))
    )
    (net (code "60") (name "Net-(IC2A-8Q)") (class "Default")
      (node (ref "IC2") (pin "19") (pinfunction "8Q_19") (pintype "tri_state"))
      (node (ref "OUT1-2") (pin "15") (pinfunction "15_15") (pintype "passive"))
    )
    (net (code "61") (name "Net-(IC3A-1Q)") (class "Default")
      (node (ref "IC3") (pin "2") (pinfunction "1Q_2") (pintype "tri_state"))
      (node (ref "OUT3-4") (pin "2") (pinfunction "2_2") (pintype "passive"))
    )
    (net (code "62") (name "Net-(IC3A-2Q)") (class "Default")
      (node (ref "IC3") (pin "5") (pinfunction "2Q_5") (pintype "tri_state"))
      (node (ref "OUT3-4") (pin "4") (pinfunction "4_4") (pintype "passive"))
    )
    (net (code "63") (name "Net-(IC3A-3Q)") (class "Default")
      (node (ref "IC3") (pin "6") (pinfunction "3Q_6") (pintype "tri_state"))
      (node (ref "OUT3-4") (pin "6") (pinfunction "6_6") (pintype "passive"))
    )
    (net (code "64") (name "Net-(IC3A-4Q)") (class "Default")
      (node (ref "IC3") (pin "9") (pinfunction "4Q_9") (pintype "tri_state"))
      (node (ref "OUT3-4") (pin "8") (pinfunction "8_8") (pintype "passive"))
    )
    (net (code "65") (name "Net-(IC3A-5Q)") (class "Default")
      (node (ref "IC3") (pin "12") (pinfunction "5Q_12") (pintype "tri_state"))
      (node (ref "OUT3-4") (pin "1") (pinfunction "1_1") (pintype "passive"))
    )
    (net (code "66") (name "Net-(IC3A-6Q)") (class "Default")
      (node (ref "IC3") (pin "15") (pinfunction "6Q_15") (pintype "tri_state"))
      (node (ref "OUT3-4") (pin "3") (pinfunction "3_3") (pintype "passive"))
    )
    (net (code "67") (name "Net-(IC3A-7Q)") (class "Default")
      (node (ref "IC3") (pin "16") (pinfunction "7Q_16") (pintype "tri_state"))
      (node (ref "OUT3-4") (pin "5") (pinfunction "5_5") (pintype "passive"))
    )
    (net (code "68") (name "Net-(IC3A-8Q)") (class "Default")
      (node (ref "IC3") (pin "19") (pinfunction "8Q_19") (pintype "tri_state"))
      (node (ref "OUT3-4") (pin "7") (pinfunction "7_7") (pintype "passive"))
    )
    (net (code "69") (name "Net-(IC4A-1Q)") (class "Default")
      (node (ref "IC4") (pin "2") (pinfunction "1Q_2") (pintype "tri_state"))
      (node (ref "OUT3-4") (pin "10") (pinfunction "10_10") (pintype "passive"))
    )
    (net (code "70") (name "Net-(IC4A-2Q)") (class "Default")
      (node (ref "IC4") (pin "5") (pinfunction "2Q_5") (pintype "tri_state"))
      (node (ref "OUT3-4") (pin "12") (pinfunction "12_12") (pintype "passive"))
    )
    (net (code "71") (name "Net-(IC4A-3Q)") (class "Default")
      (node (ref "IC4") (pin "6") (pinfunction "3Q_6") (pintype "tri_state"))
      (node (ref "OUT3-4") (pin "14") (pinfunction "14_14") (pintype "passive"))
    )
    (net (code "72") (name "Net-(IC4A-4Q)") (class "Default")
      (node (ref "IC4") (pin "9") (pinfunction "4Q_9") (pintype "tri_state"))
      (node (ref "OUT3-4") (pin "16") (pinfunction "16_16") (pintype "passive"))
    )
    (net (code "73") (name "Net-(IC4A-5Q)") (class "Default")
      (node (ref "IC4") (pin "12") (pinfunction "5Q_12") (pintype "tri_state"))
      (node (ref "OUT3-4") (pin "9") (pinfunction "9_9") (pintype "passive"))
    )
    (net (code "74") (name "Net-(IC4A-6Q)") (class "Default")
      (node (ref "IC4") (pin "15") (pinfunction "6Q_15") (pintype "tri_state"))
      (node (ref "OUT3-4") (pin "11") (pinfunction "11_11") (pintype "passive"))
    )
    (net (code "75") (name "Net-(IC4A-7Q)") (class "Default")
      (node (ref "IC4") (pin "16") (pinfunction "7Q_16") (pintype "tri_state"))
      (node (ref "OUT3-4") (pin "13") (pinfunction "13_13") (pintype "passive"))
    )
    (net (code "76") (name "Net-(IC4A-8Q)") (class "Default")
      (node (ref "IC4") (pin "19") (pinfunction "8Q_19") (pintype "tri_state"))
      (node (ref "OUT3-4") (pin "15") (pinfunction "15_15") (pintype "passive"))
    )
    (net (code "77") (name "Net-(IC5A-1Q)") (class "Default")
      (node (ref "IC5") (pin "2") (pinfunction "1Q_2") (pintype "tri_state"))
      (node (ref "OUT5-6") (pin "2") (pinfunction "2_2") (pintype "passive"))
    )
    (net (code "78") (name "Net-(IC5A-2Q)") (class "Default")
      (node (ref "IC5") (pin "5") (pinfunction "2Q_5") (pintype "tri_state"))
      (node (ref "OUT5-6") (pin "4") (pinfunction "4_4") (pintype "passive"))
    )
    (net (code "79") (name "Net-(IC5A-3Q)") (class "Default")
      (node (ref "IC5") (pin "6") (pinfunction "3Q_6") (pintype "tri_state"))
      (node (ref "OUT5-6") (pin "6") (pinfunction "6_6") (pintype "passive"))
    )
    (net (code "80") (name "Net-(IC5A-4Q)") (class "Default")
      (node (ref "IC5") (pin "9") (pinfunction "4Q_9") (pintype "tri_state"))
      (node (ref "OUT5-6") (pin "8") (pinfunction "8_8") (pintype "passive"))
    )
    (net (code "81") (name "Net-(IC5A-5Q)") (class "Default")
      (node (ref "IC5") (pin "12") (pinfunction "5Q_12") (pintype "tri_state"))
      (node (ref "OUT5-6") (pin "1") (pinfunction "1_1") (pintype "passive"))
    )
    (net (code "82") (name "Net-(IC5A-6Q)") (class "Default")
      (node (ref "IC5") (pin "15") (pinfunction "6Q_15") (pintype "tri_state"))
      (node (ref "OUT5-6") (pin "3") (pinfunction "3_3") (pintype "passive"))
    )
    (net (code "83") (name "Net-(IC5A-7Q)") (class "Default")
      (node (ref "IC5") (pin "16") (pinfunction "7Q_16") (pintype "tri_state"))
      (node (ref "OUT5-6") (pin "5") (pinfunction "5_5") (pintype "passive"))
    )
    (net (code "84") (name "Net-(IC5A-8Q)") (class "Default")
      (node (ref "IC5") (pin "19") (pinfunction "8Q_19") (pintype "tri_state"))
      (node (ref "OUT5-6") (pin "7") (pinfunction "7_7") (pintype "passive"))
    )
    (net (code "85") (name "Net-(IC6A-1Q)") (class "Default")
      (node (ref "IC6") (pin "2") (pinfunction "1Q_2") (pintype "tri_state"))
      (node (ref "OUT5-6") (pin "10") (pinfunction "10_10") (pintype "passive"))
    )
    (net (code "86") (name "Net-(IC6A-2Q)") (class "Default")
      (node (ref "IC6") (pin "5") (pinfunction "2Q_5") (pintype "tri_state"))
      (node (ref "OUT5-6") (pin "12") (pinfunction "12_12") (pintype "passive"))
    )
    (net (code "87") (name "Net-(IC6A-3Q)") (class "Default")
      (node (ref "IC6") (pin "6") (pinfunction "3Q_6") (pintype "tri_state"))
      (node (ref "OUT5-6") (pin "14") (pinfunction "14_14") (pintype "passive"))
    )
    (net (code "88") (name "Net-(IC6A-4Q)") (class "Default")
      (node (ref "IC6") (pin "9") (pinfunction "4Q_9") (pintype "tri_state"))
      (node (ref "OUT5-6") (pin "16") (pinfunction "16_16") (pintype "passive"))
    )
    (net (code "89") (name "Net-(IC6A-5Q)") (class "Default")
      (node (ref "IC6") (pin "12") (pinfunction "5Q_12") (pintype "tri_state"))
      (node (ref "OUT5-6") (pin "9") (pinfunction "9_9") (pintype "passive"))
    )
    (net (code "90") (name "Net-(IC6A-6Q)") (class "Default")
      (node (ref "IC6") (pin "15") (pinfunction "6Q_15") (pintype "tri_state"))
      (node (ref "OUT5-6") (pin "11") (pinfunction "11_11") (pintype "passive"))
    )
    (net (code "91") (name "Net-(IC6A-7Q)") (class "Default")
      (node (ref "IC6") (pin "16") (pinfunction "7Q_16") (pintype "tri_state"))
      (node (ref "OUT5-6") (pin "13") (pinfunction "13_13") (pintype "passive"))
    )
    (net (code "92") (name "Net-(IC6A-8Q)") (class "Default")
      (node (ref "IC6") (pin "19") (pinfunction "8Q_19") (pintype "tri_state"))
      (node (ref "OUT5-6") (pin "15") (pinfunction "15_15") (pintype "passive"))
    )
    (net (code "93") (name "Net-(IC7A-1Q)") (class "Default")
      (node (ref "IC7") (pin "2") (pinfunction "1Q_2") (pintype "tri_state"))
      (node (ref "OUT7-8") (pin "2") (pinfunction "2_2") (pintype "passive"))
    )
    (net (code "94") (name "Net-(IC7A-2Q)") (class "Default")
      (node (ref "IC7") (pin "5") (pinfunction "2Q_5") (pintype "tri_state"))
      (node (ref "OUT7-8") (pin "4") (pinfunction "4_4") (pintype "passive"))
    )
    (net (code "95") (name "Net-(IC7A-3Q)") (class "Default")
      (node (ref "IC7") (pin "6") (pinfunction "3Q_6") (pintype "tri_state"))
      (node (ref "OUT7-8") (pin "6") (pinfunction "6_6") (pintype "passive"))
    )
    (net (code "96") (name "Net-(IC7A-4Q)") (class "Default")
      (node (ref "IC7") (pin "9") (pinfunction "4Q_9") (pintype "tri_state"))
      (node (ref "OUT7-8") (pin "8") (pinfunction "8_8") (pintype "passive"))
    )
    (net (code "97") (name "Net-(IC7A-5Q)") (class "Default")
      (node (ref "IC7") (pin "12") (pinfunction "5Q_12") (pintype "tri_state"))
      (node (ref "OUT7-8") (pin "1") (pinfunction "1_1") (pintype "passive"))
    )
    (net (code "98") (name "Net-(IC7A-6Q)") (class "Default")
      (node (ref "IC7") (pin "15") (pinfunction "6Q_15") (pintype "tri_state"))
      (node (ref "OUT7-8") (pin "3") (pinfunction "3_3") (pintype "passive"))
    )
    (net (code "99") (name "Net-(IC7A-7Q)") (class "Default")
      (node (ref "IC7") (pin "16") (pinfunction "7Q_16") (pintype "tri_state"))
      (node (ref "OUT7-8") (pin "5") (pinfunction "5_5") (pintype "passive"))
    )
    (net (code "100") (name "Net-(IC7A-8Q)") (class "Default")
      (node (ref "IC7") (pin "19") (pinfunction "8Q_19") (pintype "tri_state"))
      (node (ref "OUT7-8") (pin "7") (pinfunction "7_7") (pintype "passive"))
    )
    (net (code "101") (name "Net-(IC8A-1Q)") (class "Default")
      (node (ref "IC8") (pin "2") (pinfunction "1Q_2") (pintype "tri_state"))
      (node (ref "OUT7-8") (pin "10") (pinfunction "10_10") (pintype "passive"))
    )
    (net (code "102") (name "Net-(IC8A-2Q)") (class "Default")
      (node (ref "IC8") (pin "5") (pinfunction "2Q_5") (pintype "tri_state"))
      (node (ref "OUT7-8") (pin "12") (pinfunction "12_12") (pintype "passive"))
    )
    (net (code "103") (name "Net-(IC8A-3Q)") (class "Default")
      (node (ref "IC8") (pin "6") (pinfunction "3Q_6") (pintype "tri_state"))
      (node (ref "OUT7-8") (pin "14") (pinfunction "14_14") (pintype "passive"))
    )
    (net (code "104") (name "Net-(IC8A-4Q)") (class "Default")
      (node (ref "IC8") (pin "9") (pinfunction "4Q_9") (pintype "tri_state"))
      (node (ref "OUT7-8") (pin "16") (pinfunction "16_16") (pintype "passive"))
    )
    (net (code "105") (name "Net-(IC8A-5Q)") (class "Default")
      (node (ref "IC8") (pin "12") (pinfunction "5Q_12") (pintype "tri_state"))
      (node (ref "OUT7-8") (pin "9") (pinfunction "9_9") (pintype "passive"))
    )
    (net (code "106") (name "Net-(IC8A-6Q)") (class "Default")
      (node (ref "IC8") (pin "15") (pinfunction "6Q_15") (pintype "tri_state"))
      (node (ref "OUT7-8") (pin "11") (pinfunction "11_11") (pintype "passive"))
    )
    (net (code "107") (name "Net-(IC8A-7Q)") (class "Default")
      (node (ref "IC8") (pin "16") (pinfunction "7Q_16") (pintype "tri_state"))
      (node (ref "OUT7-8") (pin "13") (pinfunction "13_13") (pintype "passive"))
    )
    (net (code "108") (name "Net-(IC8A-8Q)") (class "Default")
      (node (ref "IC8") (pin "19") (pinfunction "8Q_19") (pintype "tri_state"))
      (node (ref "OUT7-8") (pin "15") (pinfunction "15_15") (pintype "passive"))
    )
    (net (code "109") (name "Net-(IC11A-1D)") (class "Default")
      (node (ref "IC11") (pin "3") (pinfunction "1D_3") (pintype "input"))
      (node (ref "IN1-2") (pin "2") (pinfunction "2_2") (pintype "passive"))
    )
    (net (code "110") (name "Net-(IC11A-2D)") (class "Default")
      (node (ref "IC11") (pin "4") (pinfunction "2D_4") (pintype "input"))
      (node (ref "IN1-2") (pin "4") (pinfunction "4_4") (pintype "passive"))
    )
    (net (code "111") (name "Net-(IC11A-3D)") (class "Default")
      (node (ref "IC11") (pin "7") (pinfunction "3D_7") (pintype "input"))
      (node (ref "IN1-2") (pin "6") (pinfunction "6_6") (pintype "passive"))
    )
    (net (code "112") (name "Net-(IC11A-4D)") (class "Default")
      (node (ref "IC11") (pin "8") (pinfunction "4D_8") (pintype "input"))
      (node (ref "IN1-2") (pin "8") (pinfunction "8_8") (pintype "passive"))
    )
    (net (code "113") (name "Net-(IC11A-5D)") (class "Default")
      (node (ref "IC11") (pin "13") (pinfunction "5D_13") (pintype "input"))
      (node (ref "IN1-2") (pin "1") (pinfunction "1_1") (pintype "passive"))
    )
    (net (code "114") (name "Net-(IC11A-6D)") (class "Default")
      (node (ref "IC11") (pin "14") (pinfunction "6D_14") (pintype "input"))
      (node (ref "IN1-2") (pin "3") (pinfunction "3_3") (pintype "passive"))
    )
    (net (code "115") (name "Net-(IC11A-7D)") (class "Default")
      (node (ref "IC11") (pin "17") (pinfunction "7D_17") (pintype "input"))
      (node (ref "IN1-2") (pin "5") (pinfunction "5_5") (pintype "passive"))
    )
    (net (code "116") (name "Net-(IC11A-8D)") (class "Default")
      (node (ref "IC11") (pin "18") (pinfunction "8D_18") (pintype "input"))
      (node (ref "IN1-2") (pin "7") (pinfunction "7_7") (pintype "passive"))
    )
    (net (code "117") (name "Net-(IC12A-1D)") (class "Default")
      (node (ref "IC12") (pin "3") (pinfunction "1D_3") (pintype "input"))
      (node (ref "IN1-2") (pin "10") (pinfunction "10_10") (pintype "passive"))
    )
    (net (code "118") (name "Net-(IC12A-2D)") (class "Default")
      (node (ref "IC12") (pin "4") (pinfunction "2D_4") (pintype "input"))
      (node (ref "IN1-2") (pin "12") (pinfunction "12_12") (pintype "passive"))
    )
    (net (code "119") (name "Net-(IC12A-3D)") (class "Default")
      (node (ref "IC12") (pin "7") (pinfunction "3D_7") (pintype "input"))
      (node (ref "IN1-2") (pin "14") (pinfunction "14_14") (pintype "passive"))
    )
    (net (code "120") (name "Net-(IC12A-4D)") (class "Default")
      (node (ref "IC12") (pin "8") (pinfunction "4D_8") (pintype "input"))
      (node (ref "IN1-2") (pin "16") (pinfunction "16_16") (pintype "passive"))
    )
    (net (code "121") (name "Net-(IC12A-5D)") (class "Default")
      (node (ref "IC12") (pin "13") (pinfunction "5D_13") (pintype "input"))
      (node (ref "IN1-2") (pin "9") (pinfunction "9_9") (pintype "passive"))
    )
    (net (code "122") (name "Net-(IC12A-6D)") (class "Default")
      (node (ref "IC12") (pin "14") (pinfunction "6D_14") (pintype "input"))
      (node (ref "IN1-2") (pin "11") (pinfunction "11_11") (pintype "passive"))
    )
    (net (code "123") (name "Net-(IC12A-7D)") (class "Default")
      (node (ref "IC12") (pin "17") (pinfunction "7D_17") (pintype "input"))
      (node (ref "IN1-2") (pin "13") (pinfunction "13_13") (pintype "passive"))
    )
    (net (code "124") (name "Net-(IC12A-8D)") (class "Default")
      (node (ref "IC12") (pin "18") (pinfunction "8D_18") (pintype "input"))
      (node (ref "IN1-2") (pin "15") (pinfunction "15_15") (pintype "passive"))
    )
    (net (code "125") (name "Net-(IC13A-1D)") (class "Default")
      (node (ref "IC13") (pin "3") (pinfunction "1D_3") (pintype "input"))
      (node (ref "IN3-4") (pin "2") (pinfunction "2_2") (pintype "passive"))
    )
    (net (code "126") (name "Net-(IC13A-2D)") (class "Default")
      (node (ref "IC13") (pin "4") (pinfunction "2D_4") (pintype "input"))
      (node (ref "IN3-4") (pin "4") (pinfunction "4_4") (pintype "passive"))
    )
    (net (code "127") (name "Net-(IC13A-3D)") (class "Default")
      (node (ref "IC13") (pin "7") (pinfunction "3D_7") (pintype "input"))
      (node (ref "IN3-4") (pin "6") (pinfunction "6_6") (pintype "passive"))
    )
    (net (code "128") (name "Net-(IC13A-4D)") (class "Default")
      (node (ref "IC13") (pin "8") (pinfunction "4D_8") (pintype "input"))
      (node (ref "IN3-4") (pin "8") (pinfunction "8_8") (pintype "passive"))
    )
    (net (code "129") (name "Net-(IC13A-5D)") (class "Default")
      (node (ref "IC13") (pin "13") (pinfunction "5D_13") (pintype "input"))
      (node (ref "IN3-4") (pin "1") (pinfunction "1_1") (pintype "passive"))
    )
    (net (code "130") (name "Net-(IC13A-6D)") (class "Default")
      (node (ref "IC13") (pin "14") (pinfunction "6D_14") (pintype "input"))
      (node (ref "IN3-4") (pin "3") (pinfunction "3_3") (pintype "passive"))
    )
    (net (code "131") (name "Net-(IC13A-7D)") (class "Default")
      (node (ref "IC13") (pin "17") (pinfunction "7D_17") (pintype "input"))
      (node (ref "IN3-4") (pin "5") (pinfunction "5_5") (pintype "passive"))
    )
    (net (code "132") (name "Net-(IC13A-8D)") (class "Default")
      (node (ref "IC13") (pin "18") (pinfunction "8D_18") (pintype "input"))
      (node (ref "IN3-4") (pin "7") (pinfunction "7_7") (pintype "passive"))
    )
    (net (code "133") (name "Net-(IC14A-1D)") (class "Default")
      (node (ref "IC14") (pin "3") (pinfunction "1D_3") (pintype "input"))
      (node (ref "IN3-4") (pin "10") (pinfunction "10_10") (pintype "passive"))
    )
    (net (code "134") (name "Net-(IC14A-2D)") (class "Default")
      (node (ref "IC14") (pin "4") (pinfunction "2D_4") (pintype "input"))
      (node (ref "IN3-4") (pin "12") (pinfunction "12_12") (pintype "passive"))
    )
    (net (code "135") (name "Net-(IC14A-3D)") (class "Default")
      (node (ref "IC14") (pin "7") (pinfunction "3D_7") (pintype "input"))
      (node (ref "IN3-4") (pin "14") (pinfunction "14_14") (pintype "passive"))
    )
    (net (code "136") (name "Net-(IC14A-4D)") (class "Default")
      (node (ref "IC14") (pin "8") (pinfunction "4D_8") (pintype "input"))
      (node (ref "IN3-4") (pin "16") (pinfunction "16_16") (pintype "passive"))
    )
    (net (code "137") (name "Net-(IC14A-5D)") (class "Default")
      (node (ref "IC14") (pin "13") (pinfunction "5D_13") (pintype "input"))
      (node (ref "IN3-4") (pin "9") (pinfunction "9_9") (pintype "passive"))
    )
    (net (code "138") (name "Net-(IC14A-6D)") (class "Default")
      (node (ref "IC14") (pin "14") (pinfunction "6D_14") (pintype "input"))
      (node (ref "IN3-4") (pin "11") (pinfunction "11_11") (pintype "passive"))
    )
    (net (code "139") (name "Net-(IC14A-7D)") (class "Default")
      (node (ref "IC14") (pin "17") (pinfunction "7D_17") (pintype "input"))
      (node (ref "IN3-4") (pin "13") (pinfunction "13_13") (pintype "passive"))
    )
    (net (code "140") (name "Net-(IC14A-8D)") (class "Default")
      (node (ref "IC14") (pin "18") (pinfunction "8D_18") (pintype "input"))
      (node (ref "IN3-4") (pin "15") (pinfunction "15_15") (pintype "passive"))
    )
    (net (code "141") (name "Net-(IC15A-1D)") (class "Default")
      (node (ref "IC15") (pin "3") (pinfunction "1D_3") (pintype "input"))
      (node (ref "IN5-6") (pin "2") (pinfunction "2_2") (pintype "passive"))
    )
    (net (code "142") (name "Net-(IC15A-2D)") (class "Default")
      (node (ref "IC15") (pin "4") (pinfunction "2D_4") (pintype "input"))
      (node (ref "IN5-6") (pin "4") (pinfunction "4_4") (pintype "passive"))
    )
    (net (code "143") (name "Net-(IC15A-3D)") (class "Default")
      (node (ref "IC15") (pin "7") (pinfunction "3D_7") (pintype "input"))
      (node (ref "IN5-6") (pin "6") (pinfunction "6_6") (pintype "passive"))
    )
    (net (code "144") (name "Net-(IC15A-4D)") (class "Default")
      (node (ref "IC15") (pin "8") (pinfunction "4D_8") (pintype "input"))
      (node (ref "IN5-6") (pin "8") (pinfunction "8_8") (pintype "passive"))
    )
    (net (code "145") (name "Net-(IC15A-5D)") (class "Default")
      (node (ref "IC15") (pin "13") (pinfunction "5D_13") (pintype "input"))
      (node (ref "IN5-6") (pin "1") (pinfunction "1_1") (pintype "passive"))
    )
    (net (code "146") (name "Net-(IC15A-6D)") (class "Default")
      (node (ref "IC15") (pin "14") (pinfunction "6D_14") (pintype "input"))
      (node (ref "IN5-6") (pin "3") (pinfunction "3_3") (pintype "passive"))
    )
    (net (code "147") (name "Net-(IC15A-7D)") (class "Default")
      (node (ref "IC15") (pin "17") (pinfunction "7D_17") (pintype "input"))
      (node (ref "IN5-6") (pin "5") (pinfunction "5_5") (pintype "passive"))
    )
    (net (code "148") (name "Net-(IC15A-8D)") (class "Default")
      (node (ref "IC15") (pin "18") (pinfunction "8D_18") (pintype "input"))
      (node (ref "IN5-6") (pin "7") (pinfunction "7_7") (pintype "passive"))
    )
    (net (code "149") (name "Net-(IC16A-1D)") (class "Default")
      (node (ref "IC16") (pin "3") (pinfunction "1D_3") (pintype "input"))
      (node (ref "IN5-6") (pin "10") (pinfunction "10_10") (pintype "passive"))
    )
    (net (code "150") (name "Net-(IC16A-2D)") (class "Default")
      (node (ref "IC16") (pin "4") (pinfunction "2D_4") (pintype "input"))
      (node (ref "IN5-6") (pin "12") (pinfunction "12_12") (pintype "passive"))
    )
    (net (code "151") (name "Net-(IC16A-3D)") (class "Default")
      (node (ref "IC16") (pin "7") (pinfunction "3D_7") (pintype "input"))
      (node (ref "IN5-6") (pin "14") (pinfunction "14_14") (pintype "passive"))
    )
    (net (code "152") (name "Net-(IC16A-4D)") (class "Default")
      (node (ref "IC16") (pin "8") (pinfunction "4D_8") (pintype "input"))
      (node (ref "IN5-6") (pin "16") (pinfunction "16_16") (pintype "passive"))
    )
    (net (code "153") (name "Net-(IC16A-5D)") (class "Default")
      (node (ref "IC16") (pin "13") (pinfunction "5D_13") (pintype "input"))
      (node (ref "IN5-6") (pin "9") (pinfunction "9_9") (pintype "passive"))
    )
    (net (code "154") (name "Net-(IC16A-6D)") (class "Default")
      (node (ref "IC16") (pin "14") (pinfunction "6D_14") (pintype "input"))
      (node (ref "IN5-6") (pin "11") (pinfunction "11_11") (pintype "passive"))
    )
    (net (code "155") (name "Net-(IC16A-7D)") (class "Default")
      (node (ref "IC16") (pin "17") (pinfunction "7D_17") (pintype "input"))
      (node (ref "IN5-6") (pin "13") (pinfunction "13_13") (pintype "passive"))
    )
    (net (code "156") (name "Net-(IC16A-8D)") (class "Default")
      (node (ref "IC16") (pin "18") (pinfunction "8D_18") (pintype "input"))
      (node (ref "IN5-6") (pin "15") (pinfunction "15_15") (pintype "passive"))
    )
    (net (code "157") (name "Net-(IC17A-EXTAL)") (class "Default")
      (node (ref "C2") (pin "1") (pinfunction "1_1") (pintype "passive"))
      (node (ref "IC17") (pin "39") (pinfunction "EXTAL_39") (pintype "input"))
      (node (ref "Q1") (pin "1") (pinfunction "1_1") (pintype "passive"))
    )
    (net (code "158") (name "Net-(IC17A-XTAL)") (class "Default")
      (node (ref "C1") (pin "2") (pinfunction "2_2") (pintype "passive"))
      (node (ref "IC17") (pin "38") (pinfunction "XTAL_38") (pintype "input"))
      (node (ref "Q1") (pin "2") (pinfunction "2_2") (pintype "passive"))
    )
    (net (code "159") (name "Net-(IC18A-I0)") (class "Default")
      (node (ref "C3") (pin "1") (pinfunction "1_1") (pintype "passive"))
      (node (ref "IC18") (pin "1") (pinfunction "I0_1") (pintype "input"))
      (node (ref "R1") (pin "1") (pinfunction "1_1") (pintype "passive"))
    )
    (net (code "160") (name "Net-(IC18A-I1)") (class "Default")
      (node (ref "IC18") (pin "2") (pinfunction "I1_2") (pintype "input"))
      (node (ref "JP1") (pin "2") (pinfunction "2_2") (pintype "passive"))
      (node (ref "R2") (pin "1") (pinfunction "1_1") (pintype "passive"))
    )
    (net (code "161") (name "Net-(IC18A-O)") (class "Default")
      (node (ref "IC18") (pin "3") (pinfunction "O_3") (pintype "output"))
      (node (ref "IC18") (pin "4") (pinfunction "I0_4") (pintype "input"))
      (node (ref "IC18") (pin "5") (pinfunction "I1_5") (pintype "input"))
    )
    (net (code "162") (name "Net-(IC18C-O)") (class "Default")
      (node (ref "IC18") (pin "8") (pinfunction "O_8") (pintype "output"))
      (node (ref "IC28") (pin "1") (pinfunction "G_1") (pintype "input"))
    )
    (net (code "163") (name "Net-(IC18D-I0)") (class "Default")
      (node (ref "IC18") (pin "12") (pinfunction "I0_12") (pintype "input"))
      (node (ref "IC18") (pin "13") (pinfunction "I1_13") (pintype "input"))
      (node (ref "IC21") (pin "5") (pinfunction "RTS_5") (pintype "output"))
    )
    (net (code "164") (name "Net-(IC18D-O)") (class "Default")
      (node (ref "IC18") (pin "11") (pinfunction "O_11") (pintype "output"))
      (node (ref "LED1") (pin "K") (pinfunction "C_K") (pintype "passive"))
    )
    (net (code "165") (name "Net-(IC19A-G2B)") (class "Default")
      (node (ref "IC19") (pin "5") (pinfunction "G2B_5") (pintype "input"))
      (node (ref "IC28") (pin "4") (pinfunction "Y0_4") (pintype "output"))
    )
    (net (code "166") (name "Net-(IC20A-C1+)") (class "Default")
      (node (ref "C8") (pin "1") (pinfunction "1_1") (pintype "passive"))
      (node (ref "IC20") (pin "1") (pinfunction "C1+_1") (pintype "bidirectional"))
    )
    (net (code "167") (name "Net-(IC20A-C1-)") (class "Default")
      (node (ref "C8") (pin "2") (pinfunction "2_2") (pintype "passive"))
      (node (ref "IC20") (pin "3") (pinfunction "C1-_3") (pintype "bidirectional"))
    )
    (net (code "168") (name "Net-(IC20A-C2+)") (class "Default")
      (node (ref "C9") (pin "1") (pinfunction "1_1") (pintype "passive"))
      (node (ref "IC20") (pin "4") (pinfunction "C2+_4") (pintype "bidirectional"))
    )
    (net (code "169") (name "Net-(IC20A-C2-)") (class "Default")
      (node (ref "C9") (pin "2") (pinfunction "2_2") (pintype "passive"))
      (node (ref "IC20") (pin "5") (pinfunction "C2-_5") (pintype "bidirectional"))
    )
    (net (code "170") (name "Net-(IC20A-R2IN)") (class "Default")
      (node (ref "IC20") (pin "7") (pinfunction "T2OUT_7") (pintype "output"))
      (node (ref "IC20") (pin "8") (pinfunction "R2IN_8") (pintype "input"))
    )
    (net (code "171") (name "Net-(IC20A-V+)") (class "Default")
      (node (ref "C10") (pin "2") (pinfunction "2_2") (pintype "passive"))
      (node (ref "IC20") (pin "2") (pinfunction "V+_2") (pintype "bidirectional"))
    )
    (net (code "172") (name "Net-(IC20A-V-)") (class "Default")
      (node (ref "C11") (pin "1") (pinfunction "1_1") (pintype "passive"))
      (node (ref "IC20") (pin "6") (pinfunction "V-_6") (pintype "bidirectional"))
    )
    (net (code "173") (name "Net-(IC21A-CTS)") (class "Default")
      (node (ref "IC21") (pin "24") (pinfunction "CTS_24") (pintype "input"))
      (node (ref "JP2") (pin "1") (pinfunction "1_1") (pintype "passive"))
      (node (ref "R13") (pin "2") (pinfunction "2_2") (pintype "passive"))
    )
    (net (code "174") (name "Net-(IC21A-RXCLK)") (class "Default")
      (node (ref "IC21") (pin "3") (pinfunction "RXCLK_3") (pintype "input"))
      (node (ref "IC21") (pin "4") (pinfunction "TXCLK_4") (pintype "input"))
      (node (ref "IC27") (pin "5") (pinfunction "Q_5") (pintype "output"))
    )
    (net (code "175") (name "Net-(IC24A-CA1)") (class "Default")
      (node (ref "IC24") (pin "40") (pinfunction "CA1_40") (pintype "input"))
      (node (ref "IC27") (pin "9") (pinfunction "Q_9") (pintype "output"))
    )
    (net (code "176") (name "Net-(IC24A-CA2)") (class "Default")
      (node (ref "IC24") (pin "39") (pinfunction "CA2_39") (pintype "bidirectional"))
      (node (ref "IC25") (pin "1") (pinfunction "DIR_1") (pintype "input"))
    )
    (net (code "177") (name "Net-(IC24A-CB2)") (class "Default")
      (node (ref "IC24") (pin "19") (pinfunction "CB2_19") (pintype "bidirectional"))
      (node (ref "IC26") (pin "1") (pinfunction "DIR_1") (pintype "input"))
    )
    (net (code "178") (name "Net-(IC24A-PA0)") (class "Default")
      (node (ref "IC24") (pin "2") (pinfunction "PA0_2") (pintype "bidirectional"))
      (node (ref "IC25") (pin "18") (pinfunction "B1_18") (pintype "bidirectional"))
    )
    (net (code "179") (name "Net-(IC24A-PA1)") (class "Default")
      (node (ref "IC24") (pin "3") (pinfunction "PA1_3") (pintype "bidirectional"))
      (node (ref "IC25") (pin "17") (pinfunction "B2_17") (pintype "bidirectional"))
    )
    (net (code "180") (name "Net-(IC24A-PA2)") (class "Default")
      (node (ref "IC24") (pin "4") (pinfunction "PA2_4") (pintype "bidirectional"))
      (node (ref "IC25") (pin "16") (pinfunction "B3_16") (pintype "bidirectional"))
    )
    (net (code "181") (name "Net-(IC24A-PA3)") (class "Default")
      (node (ref "IC24") (pin "5") (pinfunction "PA3_5") (pintype "bidirectional"))
      (node (ref "IC25") (pin "15") (pinfunction "B4_15") (pintype "bidirectional"))
    )
    (net (code "182") (name "Net-(IC24A-PA4)") (class "Default")
      (node (ref "IC24") (pin "6") (pinfunction "PA4_6") (pintype "bidirectional"))
      (node (ref "IC25") (pin "14") (pinfunction "B5_14") (pintype "bidirectional"))
    )
    (net (code "183") (name "Net-(IC24A-PA5)") (class "Default")
      (node (ref "IC24") (pin "7") (pinfunction "PA5_7") (pintype "bidirectional"))
      (node (ref "IC25") (pin "13") (pinfunction "B6_13") (pintype "bidirectional"))
    )
    (net (code "184") (name "Net-(IC24A-PA6)") (class "Default")
      (node (ref "IC24") (pin "8") (pinfunction "PA6_8") (pintype "bidirectional"))
      (node (ref "IC25") (pin "12") (pinfunction "B7_12") (pintype "bidirectional"))
    )
    (net (code "185") (name "Net-(IC24A-PA7)") (class "Default")
      (node (ref "IC24") (pin "9") (pinfunction "PA7_9") (pintype "bidirectional"))
      (node (ref "IC25") (pin "11") (pinfunction "B8_11") (pintype "bidirectional"))
    )
    (net (code "186") (name "Net-(IC24A-PB0)") (class "Default")
      (node (ref "IC24") (pin "10") (pinfunction "PB0_10") (pintype "bidirectional"))
      (node (ref "IC26") (pin "18") (pinfunction "B1_18") (pintype "bidirectional"))
    )
    (net (code "187") (name "Net-(IC24A-PB1)") (class "Default")
      (node (ref "IC24") (pin "11") (pinfunction "PB1_11") (pintype "bidirectional"))
      (node (ref "IC26") (pin "17") (pinfunction "B2_17") (pintype "bidirectional"))
    )
    (net (code "188") (name "Net-(IC24A-PB2)") (class "Default")
      (node (ref "IC24") (pin "12") (pinfunction "PB2_12") (pintype "bidirectional"))
      (node (ref "IC26") (pin "16") (pinfunction "B3_16") (pintype "bidirectional"))
    )
    (net (code "189") (name "Net-(IC24A-PB3)") (class "Default")
      (node (ref "IC24") (pin "13") (pinfunction "PB3_13") (pintype "bidirectional"))
      (node (ref "IC26") (pin "15") (pinfunction "B4_15") (pintype "bidirectional"))
    )
    (net (code "190") (name "Net-(IC24A-PB4)") (class "Default")
      (node (ref "IC24") (pin "14") (pinfunction "PB4_14") (pintype "bidirectional"))
      (node (ref "IC26") (pin "14") (pinfunction "B5_14") (pintype "bidirectional"))
    )
    (net (code "191") (name "Net-(IC24A-PB5)") (class "Default")
      (node (ref "IC24") (pin "15") (pinfunction "PB5_15") (pintype "bidirectional"))
      (node (ref "IC26") (pin "13") (pinfunction "B6_13") (pintype "bidirectional"))
    )
    (net (code "192") (name "Net-(IC24A-PB6)") (class "Default")
      (node (ref "IC24") (pin "16") (pinfunction "PB6_16") (pintype "bidirectional"))
      (node (ref "IC26") (pin "12") (pinfunction "B7_12") (pintype "bidirectional"))
    )
    (net (code "193") (name "Net-(IC24A-PB7)") (class "Default")
      (node (ref "IC24") (pin "17") (pinfunction "PB7_17") (pintype "bidirectional"))
      (node (ref "IC26") (pin "11") (pinfunction "B8_11") (pintype "bidirectional"))
    )
    (net (code "194") (name "Net-(IC27A-CV)") (class "Default")
      (node (ref "C7") (pin "1") (pinfunction "1_1") (pintype "passive"))
      (node (ref "IC27") (pin "3") (pinfunction "CV_3") (pintype "input"))
    )
    (net (code "195") (name "Net-(IC27A-DIS)") (class "Default")
      (node (ref "IC27") (pin "1") (pinfunction "DIS_1") (pintype "input"))
      (node (ref "R10") (pin "2") (pinfunction "2_2") (pintype "passive"))
      (node (ref "R9") (pin "1") (pinfunction "1_1") (pintype "passive"))
    )
    (net (code "196") (name "Net-(IC27A-THR)") (class "Default")
      (node (ref "C6") (pin "1") (pinfunction "1_1") (pintype "passive"))
      (node (ref "IC27") (pin "2") (pinfunction "THR_2") (pintype "input"))
      (node (ref "IC27") (pin "6") (pinfunction "TR_6") (pintype "input"))
      (node (ref "R11") (pin "A") (pinfunction "A_A") (pintype "passive"))
      (node (ref "R11") (pin "S") (pinfunction "S_S") (pintype "passive"))
    )
    (net (code "197") (name "Net-(IC27B-CV)") (class "Default")
      (node (ref "C5") (pin "1") (pinfunction "1_1") (pintype "passive"))
      (node (ref "IC27") (pin "11") (pinfunction "CV_11") (pintype "input"))
    )
    (net (code "198") (name "Net-(IC27B-DIS)") (class "Default")
      (node (ref "IC27") (pin "13") (pinfunction "DIS_13") (pintype "input"))
      (node (ref "R3") (pin "1") (pinfunction "1_1") (pintype "passive"))
      (node (ref "R4") (pin "2") (pinfunction "2_2") (pintype "passive"))
    )
    (net (code "199") (name "Net-(IC27B-THR)") (class "Default")
      (node (ref "C4") (pin "1") (pinfunction "1_1") (pintype "passive"))
      (node (ref "IC27") (pin "12") (pinfunction "THR_12") (pintype "input"))
      (node (ref "IC27") (pin "8") (pinfunction "TR_8") (pintype "input"))
      (node (ref "R4") (pin "1") (pinfunction "1_1") (pintype "passive"))
    )
    (net (code "200") (name "Net-(LED1-PadA)") (class "Default")
      (node (ref "LED1") (pin "A") (pinfunction "A_A") (pintype "passive"))
      (node (ref "R12") (pin "1") (pinfunction "1_1") (pintype "passive"))
    )
    (net (code "201") (name "Net-(R10-Pad1)") (class "Default")
      (node (ref "R10") (pin "1") (pinfunction "1_1") (pintype "passive"))
      (node (ref "R11") (pin "E") (pinfunction "E_E") (pintype "passive"))
    )
    (net (code "202") (name "Net-(X1-Pad4)") (class "Default")
      (node (ref "X1") (pin "4") (pinfunction "4_4") (pintype "passive"))
      (node (ref "X1") (pin "6") (pinfunction "6_6") (pintype "passive"))
    )
    (net (code "203") (name "Net-(X1-Pad7)") (class "Default")
      (node (ref "X1") (pin "7") (pinfunction "7_7") (pintype "passive"))
      (node (ref "X1") (pin "8") (pinfunction "8_8") (pintype "passive"))
    )
    (net (code "204") (name "OUT00") (class "Default")
      (node (ref "IC1") (pin "11") (pinfunction "CLK_11") (pintype "input"))
      (node (ref "IC10") (pin "1") (pinfunction "0_1") (pintype "output"))
    )
    (net (code "205") (name "OUT01") (class "Default")
      (node (ref "IC10") (pin "2") (pinfunction "1_2") (pintype "output"))
      (node (ref "IC2") (pin "11") (pinfunction "CLK_11") (pintype "input"))
    )
    (net (code "206") (name "OUT02") (class "Default")
      (node (ref "IC10") (pin "3") (pinfunction "2_3") (pintype "output"))
      (node (ref "IC3") (pin "11") (pinfunction "CLK_11") (pintype "input"))
    )
    (net (code "207") (name "OUT03") (class "Default")
      (node (ref "IC10") (pin "4") (pinfunction "3_4") (pintype "output"))
      (node (ref "IC4") (pin "11") (pinfunction "CLK_11") (pintype "input"))
    )
    (net (code "208") (name "OUT04") (class "Default")
      (node (ref "IC10") (pin "5") (pinfunction "4_5") (pintype "output"))
      (node (ref "IC5") (pin "11") (pinfunction "CLK_11") (pintype "input"))
    )
    (net (code "209") (name "OUT05") (class "Default")
      (node (ref "IC10") (pin "6") (pinfunction "5_6") (pintype "output"))
      (node (ref "IC6") (pin "11") (pinfunction "CLK_11") (pintype "input"))
    )
    (net (code "210") (name "OUT06") (class "Default")
      (node (ref "IC10") (pin "7") (pinfunction "6_7") (pintype "output"))
      (node (ref "IC7") (pin "11") (pinfunction "CLK_11") (pintype "input"))
    )
    (net (code "211") (name "OUT07") (class "Default")
      (node (ref "IC10") (pin "8") (pinfunction "7_8") (pintype "output"))
      (node (ref "IC8") (pin "11") (pinfunction "CLK_11") (pintype "input"))
    )
    (net (code "212") (name "OUT08") (class "Default")
      (node (ref "IC10") (pin "9") (pinfunction "8_9") (pintype "output"))
    )
    (net (code "213") (name "OUT09") (class "Default")
      (node (ref "IC10") (pin "10") (pinfunction "9_10") (pintype "output"))
    )
    (net (code "214") (name "OUT10") (class "Default")
      (node (ref "IC10") (pin "11") (pinfunction "10_11") (pintype "output"))
    )
    (net (code "215") (name "OUT11") (class "Default")
      (node (ref "IC10") (pin "13") (pinfunction "11_13") (pintype "output"))
    )
    (net (code "216") (name "OUT12") (class "Default")
      (node (ref "IC10") (pin "14") (pinfunction "12_14") (pintype "output"))
    )
    (net (code "217") (name "OUT13") (class "Default")
      (node (ref "IC10") (pin "15") (pinfunction "13_15") (pintype "output"))
    )
    (net (code "218") (name "OUT14") (class "Default")
      (node (ref "IC10") (pin "16") (pinfunction "14_16") (pintype "output"))
    )
    (net (code "219") (name "OUT15") (class "Default")
      (node (ref "IC10") (pin "17") (pinfunction "15_17") (pintype "output"))
    )
    (net (code "220") (name "PIA-A0") (class "Default")
      (node (ref "IC1") (pin "3") (pinfunction "1D_3") (pintype "input"))
      (node (ref "IC11") (pin "2") (pinfunction "1Q_2") (pintype "tri_state"))
      (node (ref "IC12") (pin "2") (pinfunction "1Q_2") (pintype "tri_state"))
      (node (ref "IC13") (pin "2") (pinfunction "1Q_2") (pintype "tri_state"))
      (node (ref "IC14") (pin "2") (pinfunction "1Q_2") (pintype "tri_state"))
      (node (ref "IC15") (pin "2") (pinfunction "1Q_2") (pintype "tri_state"))
      (node (ref "IC16") (pin "2") (pinfunction "1Q_2") (pintype "tri_state"))
      (node (ref "IC2") (pin "3") (pinfunction "1D_3") (pintype "input"))
      (node (ref "IC25") (pin "2") (pinfunction "A1_2") (pintype "bidirectional"))
      (node (ref "IC3") (pin "3") (pinfunction "1D_3") (pintype "input"))
      (node (ref "IC4") (pin "3") (pinfunction "1D_3") (pintype "input"))
      (node (ref "IC5") (pin "3") (pinfunction "1D_3") (pintype "input"))
      (node (ref "IC6") (pin "3") (pinfunction "1D_3") (pintype "input"))
      (node (ref "IC7") (pin "3") (pinfunction "1D_3") (pintype "input"))
      (node (ref "IC8") (pin "3") (pinfunction "1D_3") (pintype "input"))
      (node (ref "SV9") (pin "1") (pinfunction "1_1") (pintype "passive"))
    )
    (net (code "221") (name "PIA-A1") (class "Default")
      (node (ref "IC1") (pin "4") (pinfunction "2D_4") (pintype "input"))
      (node (ref "IC11") (pin "5") (pinfunction "2Q_5") (pintype "tri_state"))
      (node (ref "IC12") (pin "5") (pinfunction "2Q_5") (pintype "tri_state"))
      (node (ref "IC13") (pin "5") (pinfunction "2Q_5") (pintype "tri_state"))
      (node (ref "IC14") (pin "5") (pinfunction "2Q_5") (pintype "tri_state"))
      (node (ref "IC15") (pin "5") (pinfunction "2Q_5") (pintype "tri_state"))
      (node (ref "IC16") (pin "5") (pinfunction "2Q_5") (pintype "tri_state"))
      (node (ref "IC2") (pin "4") (pinfunction "2D_4") (pintype "input"))
      (node (ref "IC25") (pin "3") (pinfunction "A2_3") (pintype "bidirectional"))
      (node (ref "IC3") (pin "4") (pinfunction "2D_4") (pintype "input"))
      (node (ref "IC4") (pin "4") (pinfunction "2D_4") (pintype "input"))
      (node (ref "IC5") (pin "4") (pinfunction "2D_4") (pintype "input"))
      (node (ref "IC6") (pin "4") (pinfunction "2D_4") (pintype "input"))
      (node (ref "IC7") (pin "4") (pinfunction "2D_4") (pintype "input"))
      (node (ref "IC8") (pin "4") (pinfunction "2D_4") (pintype "input"))
      (node (ref "SV9") (pin "2") (pinfunction "2_2") (pintype "passive"))
    )
    (net (code "222") (name "PIA-A2") (class "Default")
      (node (ref "IC1") (pin "7") (pinfunction "3D_7") (pintype "input"))
      (node (ref "IC11") (pin "6") (pinfunction "3Q_6") (pintype "tri_state"))
      (node (ref "IC12") (pin "6") (pinfunction "3Q_6") (pintype "tri_state"))
      (node (ref "IC13") (pin "6") (pinfunction "3Q_6") (pintype "tri_state"))
      (node (ref "IC14") (pin "6") (pinfunction "3Q_6") (pintype "tri_state"))
      (node (ref "IC15") (pin "6") (pinfunction "3Q_6") (pintype "tri_state"))
      (node (ref "IC16") (pin "6") (pinfunction "3Q_6") (pintype "tri_state"))
      (node (ref "IC2") (pin "7") (pinfunction "3D_7") (pintype "input"))
      (node (ref "IC25") (pin "4") (pinfunction "A3_4") (pintype "bidirectional"))
      (node (ref "IC3") (pin "7") (pinfunction "3D_7") (pintype "input"))
      (node (ref "IC4") (pin "7") (pinfunction "3D_7") (pintype "input"))
      (node (ref "IC5") (pin "7") (pinfunction "3D_7") (pintype "input"))
      (node (ref "IC6") (pin "7") (pinfunction "3D_7") (pintype "input"))
      (node (ref "IC7") (pin "7") (pinfunction "3D_7") (pintype "input"))
      (node (ref "IC8") (pin "7") (pinfunction "3D_7") (pintype "input"))
      (node (ref "SV9") (pin "3") (pinfunction "3_3") (pintype "passive"))
    )
    (net (code "223") (name "PIA-A3") (class "Default")
      (node (ref "IC1") (pin "8") (pinfunction "4D_8") (pintype "input"))
      (node (ref "IC11") (pin "9") (pinfunction "4Q_9") (pintype "tri_state"))
      (node (ref "IC12") (pin "9") (pinfunction "4Q_9") (pintype "tri_state"))
      (node (ref "IC13") (pin "9") (pinfunction "4Q_9") (pintype "tri_state"))
      (node (ref "IC14") (pin "9") (pinfunction "4Q_9") (pintype "tri_state"))
      (node (ref "IC15") (pin "9") (pinfunction "4Q_9") (pintype "tri_state"))
      (node (ref "IC16") (pin "9") (pinfunction "4Q_9") (pintype "tri_state"))
      (node (ref "IC2") (pin "8") (pinfunction "4D_8") (pintype "input"))
      (node (ref "IC25") (pin "5") (pinfunction "A4_5") (pintype "bidirectional"))
      (node (ref "IC3") (pin "8") (pinfunction "4D_8") (pintype "input"))
      (node (ref "IC4") (pin "8") (pinfunction "4D_8") (pintype "input"))
      (node (ref "IC5") (pin "8") (pinfunction "4D_8") (pintype "input"))
      (node (ref "IC6") (pin "8") (pinfunction "4D_8") (pintype "input"))
      (node (ref "IC7") (pin "8") (pinfunction "4D_8") (pintype "input"))
      (node (ref "IC8") (pin "8") (pinfunction "4D_8") (pintype "input"))
      (node (ref "SV9") (pin "4") (pinfunction "4_4") (pintype "passive"))
    )
    (net (code "224") (name "PIA-A4") (class "Default")
      (node (ref "IC1") (pin "13") (pinfunction "5D_13") (pintype "input"))
      (node (ref "IC11") (pin "12") (pinfunction "5Q_12") (pintype "tri_state"))
      (node (ref "IC12") (pin "12") (pinfunction "5Q_12") (pintype "tri_state"))
      (node (ref "IC13") (pin "12") (pinfunction "5Q_12") (pintype "tri_state"))
      (node (ref "IC14") (pin "12") (pinfunction "5Q_12") (pintype "tri_state"))
      (node (ref "IC15") (pin "12") (pinfunction "5Q_12") (pintype "tri_state"))
      (node (ref "IC16") (pin "12") (pinfunction "5Q_12") (pintype "tri_state"))
      (node (ref "IC2") (pin "13") (pinfunction "5D_13") (pintype "input"))
      (node (ref "IC25") (pin "6") (pinfunction "A5_6") (pintype "bidirectional"))
      (node (ref "IC3") (pin "13") (pinfunction "5D_13") (pintype "input"))
      (node (ref "IC4") (pin "13") (pinfunction "5D_13") (pintype "input"))
      (node (ref "IC5") (pin "13") (pinfunction "5D_13") (pintype "input"))
      (node (ref "IC6") (pin "13") (pinfunction "5D_13") (pintype "input"))
      (node (ref "IC7") (pin "13") (pinfunction "5D_13") (pintype "input"))
      (node (ref "IC8") (pin "13") (pinfunction "5D_13") (pintype "input"))
      (node (ref "SV9") (pin "5") (pinfunction "5_5") (pintype "passive"))
    )
    (net (code "225") (name "PIA-A5") (class "Default")
      (node (ref "IC1") (pin "14") (pinfunction "6D_14") (pintype "input"))
      (node (ref "IC11") (pin "15") (pinfunction "6Q_15") (pintype "tri_state"))
      (node (ref "IC12") (pin "15") (pinfunction "6Q_15") (pintype "tri_state"))
      (node (ref "IC13") (pin "15") (pinfunction "6Q_15") (pintype "tri_state"))
      (node (ref "IC14") (pin "15") (pinfunction "6Q_15") (pintype "tri_state"))
      (node (ref "IC15") (pin "15") (pinfunction "6Q_15") (pintype "tri_state"))
      (node (ref "IC16") (pin "15") (pinfunction "6Q_15") (pintype "tri_state"))
      (node (ref "IC2") (pin "14") (pinfunction "6D_14") (pintype "input"))
      (node (ref "IC25") (pin "7") (pinfunction "A6_7") (pintype "bidirectional"))
      (node (ref "IC3") (pin "14") (pinfunction "6D_14") (pintype "input"))
      (node (ref "IC4") (pin "14") (pinfunction "6D_14") (pintype "input"))
      (node (ref "IC5") (pin "14") (pinfunction "6D_14") (pintype "input"))
      (node (ref "IC6") (pin "14") (pinfunction "6D_14") (pintype "input"))
      (node (ref "IC7") (pin "14") (pinfunction "6D_14") (pintype "input"))
      (node (ref "IC8") (pin "14") (pinfunction "6D_14") (pintype "input"))
      (node (ref "SV9") (pin "6") (pinfunction "6_6") (pintype "passive"))
    )
    (net (code "226") (name "PIA-A6") (class "Default")
      (node (ref "IC1") (pin "17") (pinfunction "7D_17") (pintype "input"))
      (node (ref "IC11") (pin "16") (pinfunction "7Q_16") (pintype "tri_state"))
      (node (ref "IC12") (pin "16") (pinfunction "7Q_16") (pintype "tri_state"))
      (node (ref "IC13") (pin "16") (pinfunction "7Q_16") (pintype "tri_state"))
      (node (ref "IC14") (pin "16") (pinfunction "7Q_16") (pintype "tri_state"))
      (node (ref "IC15") (pin "16") (pinfunction "7Q_16") (pintype "tri_state"))
      (node (ref "IC16") (pin "16") (pinfunction "7Q_16") (pintype "tri_state"))
      (node (ref "IC2") (pin "17") (pinfunction "7D_17") (pintype "input"))
      (node (ref "IC25") (pin "8") (pinfunction "A7_8") (pintype "bidirectional"))
      (node (ref "IC3") (pin "17") (pinfunction "7D_17") (pintype "input"))
      (node (ref "IC4") (pin "17") (pinfunction "7D_17") (pintype "input"))
      (node (ref "IC5") (pin "17") (pinfunction "7D_17") (pintype "input"))
      (node (ref "IC6") (pin "17") (pinfunction "7D_17") (pintype "input"))
      (node (ref "IC7") (pin "17") (pinfunction "7D_17") (pintype "input"))
      (node (ref "IC8") (pin "17") (pinfunction "7D_17") (pintype "input"))
      (node (ref "SV9") (pin "7") (pinfunction "7_7") (pintype "passive"))
    )
    (net (code "227") (name "PIA-A7") (class "Default")
      (node (ref "IC1") (pin "18") (pinfunction "8D_18") (pintype "input"))
      (node (ref "IC11") (pin "19") (pinfunction "8Q_19") (pintype "tri_state"))
      (node (ref "IC12") (pin "19") (pinfunction "8Q_19") (pintype "tri_state"))
      (node (ref "IC13") (pin "19") (pinfunction "8Q_19") (pintype "tri_state"))
      (node (ref "IC14") (pin "19") (pinfunction "8Q_19") (pintype "tri_state"))
      (node (ref "IC15") (pin "19") (pinfunction "8Q_19") (pintype "tri_state"))
      (node (ref "IC16") (pin "19") (pinfunction "8Q_19") (pintype "tri_state"))
      (node (ref "IC2") (pin "18") (pinfunction "8D_18") (pintype "input"))
      (node (ref "IC25") (pin "9") (pinfunction "A8_9") (pintype "bidirectional"))
      (node (ref "IC3") (pin "18") (pinfunction "8D_18") (pintype "input"))
      (node (ref "IC4") (pin "18") (pinfunction "8D_18") (pintype "input"))
      (node (ref "IC5") (pin "18") (pinfunction "8D_18") (pintype "input"))
      (node (ref "IC6") (pin "18") (pinfunction "8D_18") (pintype "input"))
      (node (ref "IC7") (pin "18") (pinfunction "8D_18") (pintype "input"))
      (node (ref "IC8") (pin "18") (pinfunction "8D_18") (pintype "input"))
      (node (ref "SV9") (pin "8") (pinfunction "8_8") (pintype "passive"))
    )
    (net (code "228") (name "PIA-B0") (class "Default")
      (node (ref "IC10") (pin "23") (pinfunction "A_23") (pintype "input"))
      (node (ref "IC26") (pin "2") (pinfunction "A1_2") (pintype "bidirectional"))
      (node (ref "IC9") (pin "23") (pinfunction "A_23") (pintype "input"))
      (node (ref "SV9") (pin "13") (pinfunction "13_13") (pintype "passive"))
    )
    (net (code "229") (name "PIA-B1") (class "Default")
      (node (ref "IC10") (pin "22") (pinfunction "B_22") (pintype "input"))
      (node (ref "IC26") (pin "3") (pinfunction "A2_3") (pintype "bidirectional"))
      (node (ref "IC9") (pin "22") (pinfunction "B_22") (pintype "input"))
      (node (ref "SV9") (pin "14") (pinfunction "14_14") (pintype "passive"))
    )
    (net (code "230") (name "PIA-B2") (class "Default")
      (node (ref "IC10") (pin "21") (pinfunction "C_21") (pintype "input"))
      (node (ref "IC26") (pin "4") (pinfunction "A3_4") (pintype "bidirectional"))
      (node (ref "IC9") (pin "21") (pinfunction "C_21") (pintype "input"))
      (node (ref "SV9") (pin "15") (pinfunction "15_15") (pintype "passive"))
    )
    (net (code "231") (name "PIA-B3") (class "Default")
      (node (ref "IC10") (pin "20") (pinfunction "D_20") (pintype "input"))
      (node (ref "IC26") (pin "5") (pinfunction "A4_5") (pintype "bidirectional"))
      (node (ref "IC9") (pin "20") (pinfunction "D_20") (pintype "input"))
      (node (ref "SV9") (pin "16") (pinfunction "16_16") (pintype "passive"))
    )
    (net (code "232") (name "PIA-B4") (class "Default")
      (node (ref "IC26") (pin "6") (pinfunction "A5_6") (pintype "bidirectional"))
      (node (ref "IC9") (pin "18") (pinfunction "G1_18") (pintype "input"))
      (node (ref "SV9") (pin "17") (pinfunction "17_17") (pintype "passive"))
    )
    (net (code "233") (name "PIA-B5") (class "Default")
      (node (ref "IC10") (pin "18") (pinfunction "G1_18") (pintype "input"))
      (node (ref "IC26") (pin "7") (pinfunction "A6_7") (pintype "bidirectional"))
      (node (ref "SV9") (pin "18") (pinfunction "18_18") (pintype "passive"))
    )
    (net (code "234") (name "PIA-B6") (class "Default")
      (node (ref "IC26") (pin "8") (pinfunction "A7_8") (pintype "bidirectional"))
      (node (ref "SV9") (pin "19") (pinfunction "19_19") (pintype "passive"))
    )
    (net (code "235") (name "PIA-B7") (class "Default")
      (node (ref "IC26") (pin "9") (pinfunction "A8_9") (pintype "bidirectional"))
      (node (ref "SV9") (pin "20") (pinfunction "20_20") (pintype "passive"))
    )
    (net (code "236") (name "RX") (class "Default")
      (node (ref "IC20") (pin "12") (pinfunction "R1OUT_12") (pintype "output"))
      (node (ref "IC21") (pin "2") (pinfunction "RXDATA_2") (pintype "input"))
    )
    (net (code "237") (name "RXD") (class "Default")
      (node (ref "IC20") (pin "13") (pinfunction "R1IN_13") (pintype "input"))
      (node (ref "X1") (pin "3") (pinfunction "3_3") (pintype "passive"))
    )
    (net (code "238") (name "R{slash}~{W}") (class "Default")
      (node (ref "IC17") (pin "34") (pinfunction "R/~{W}_34") (pintype "output"))
      (node (ref "IC21") (pin "13") (pinfunction "R/~{W}_13") (pintype "input"))
      (node (ref "IC22") (pin "27") (pinfunction "~{WE}_27") (pintype "input"))
      (node (ref "IC24") (pin "21") (pinfunction "R/~{W}_21") (pintype "input"))
    )
    (net (code "239") (name "TX") (class "Default")
      (node (ref "IC20") (pin "11") (pinfunction "T1IN_11") (pintype "input"))
      (node (ref "IC21") (pin "6") (pinfunction "TXDATA_6") (pintype "output"))
    )
    (net (code "240") (name "TXD") (class "Default")
      (node (ref "IC20") (pin "14") (pinfunction "T1OUT_14") (pintype "output"))
      (node (ref "X1") (pin "2") (pinfunction "2_2") (pintype "passive"))
    )
    (net (code "241") (name "VCC") (class "Default")
      (node (ref "BYP1") (pin "1") (pinfunction "1_1") (pintype "passive"))
      (node (ref "BYP10") (pin "1") (pinfunction "1_1") (pintype "passive"))
      (node (ref "BYP11") (pin "1") (pinfunction "1_1") (pintype "passive"))
      (node (ref "BYP12") (pin "1") (pinfunction "1_1") (pintype "passive"))
      (node (ref "BYP13") (pin "1") (pinfunction "1_1") (pintype "passive"))
      (node (ref "BYP14") (pin "1") (pinfunction "1_1") (pintype "passive"))
      (node (ref "BYP15") (pin "1") (pinfunction "1_1") (pintype "passive"))
      (node (ref "BYP16") (pin "1") (pinfunction "1_1") (pintype "passive"))
      (node (ref "BYP17") (pin "1") (pinfunction "1_1") (pintype "passive"))
      (node (ref "BYP18") (pin "1") (pinfunction "1_1") (pintype "passive"))
      (node (ref "BYP19") (pin "1") (pinfunction "1_1") (pintype "passive"))
      (node (ref "BYP2") (pin "1") (pinfunction "1_1") (pintype "passive"))
      (node (ref "BYP20") (pin "1") (pinfunction "1_1") (pintype "passive"))
      (node (ref "BYP21") (pin "1") (pinfunction "1_1") (pintype "passive"))
      (node (ref "BYP22") (pin "1") (pinfunction "1_1") (pintype "passive"))
      (node (ref "BYP23") (pin "1") (pinfunction "1_1") (pintype "passive"))
      (node (ref "BYP24") (pin "1") (pinfunction "1_1") (pintype "passive"))
      (node (ref "BYP25") (pin "1") (pinfunction "1_1") (pintype "passive"))
      (node (ref "BYP26") (pin "1") (pinfunction "1_1") (pintype "passive"))
      (node (ref "BYP27") (pin "1") (pinfunction "1_1") (pintype "passive"))
      (node (ref "BYP28") (pin "1") (pinfunction "1_1") (pintype "passive"))
      (node (ref "BYP3") (pin "1") (pinfunction "1_1") (pintype "passive"))
      (node (ref "BYP4") (pin "1") (pinfunction "1_1") (pintype "passive"))
      (node (ref "BYP5") (pin "1") (pinfunction "1_1") (pintype "passive"))
      (node (ref "BYP6") (pin "1") (pinfunction "1_1") (pintype "passive"))
      (node (ref "BYP7") (pin "1") (pinfunction "1_1") (pintype "passive"))
      (node (ref "BYP8") (pin "1") (pinfunction "1_1") (pintype "passive"))
      (node (ref "BYP9") (pin "1") (pinfunction "1_1") (pintype "passive"))
      (node (ref "C10") (pin "1") (pinfunction "1_1") (pintype "passive"))
      (node (ref "IC11") (pin "11") (pinfunction "ENC_11") (pintype "input"))
      (node (ref "IC12") (pin "11") (pinfunction "ENC_11") (pintype "input"))
      (node (ref "IC13") (pin "11") (pinfunction "ENC_11") (pintype "input"))
      (node (ref "IC14") (pin "11") (pinfunction "ENC_11") (pintype "input"))
      (node (ref "IC15") (pin "11") (pinfunction "ENC_11") (pintype "input"))
      (node (ref "IC16") (pin "11") (pinfunction "ENC_11") (pintype "input"))
      (node (ref "IC17") (pin "35") (pinfunction "VCCSTB_35") (pintype "input"))
      (node (ref "IC17") (pin "36") (pinfunction "RE_36") (pintype "input"))
      (node (ref "IC17") (pin "8") (pinfunction "VCC_8") (pintype "power_in"))
      (node (ref "IC21") (pin "10") (pinfunction "CS1_10") (pintype "input"))
      (node (ref "IC21") (pin "12") (pinfunction "VCC_12") (pintype "power_in"))
      (node (ref "IC21") (pin "8") (pinfunction "CS0_8") (pintype "input"))
      (node (ref "IC22") (pin "26") (pinfunction "CS2_26") (pintype "input"))
      (node (ref "IC22") (pin "28") (pinfunction "VCC_28") (pintype "power_in"))
      (node (ref "IC23") (pin "1") (pinfunction "VPP_1") (pintype "input"))
      (node (ref "IC23") (pin "27") (pinfunction "~{PGM}_27") (pintype "passive"))
      (node (ref "IC23") (pin "28") (pinfunction "VCC_28") (pintype "power_in"))
      (node (ref "IC24") (pin "20") (pinfunction "VCC_20") (pintype "power_in"))
      (node (ref "IC24") (pin "22") (pinfunction "CS0_22") (pintype "input"))
      (node (ref "IC24") (pin "24") (pinfunction "CS1_24") (pintype "input"))
      (node (ref "IC27") (pin "10") (pinfunction "R_10") (pintype "input"))
      (node (ref "IC27") (pin "14") (pinfunction "V+_14") (pintype "power_in"))
      (node (ref "IC27") (pin "4") (pinfunction "R_4") (pintype "input"))
      (node (ref "JP2") (pin "2") (pinfunction "2_2") (pintype "passive"))
      (node (ref "R1") (pin "2") (pinfunction "2_2") (pintype "passive"))
      (node (ref "R12") (pin "2") (pinfunction "2_2") (pintype "passive"))
      (node (ref "R14") (pin "2") (pinfunction "2_2") (pintype "passive"))
      (node (ref "R2") (pin "2") (pinfunction "2_2") (pintype "passive"))
      (node (ref "R3") (pin "2") (pinfunction "2_2") (pintype "passive"))
      (node (ref "R5") (pin "2") (pinfunction "2_2") (pintype "passive"))
      (node (ref "R6") (pin "2") (pinfunction "2_2") (pintype "passive"))
      (node (ref "R7") (pin "2") (pinfunction "2_2") (pintype "passive"))
      (node (ref "R8") (pin "2") (pinfunction "2_2") (pintype "passive"))
      (node (ref "R9") (pin "2") (pinfunction "2_2") (pintype "passive"))
      (node (ref "SV9") (pin "11") (pinfunction "11_11") (pintype "passive"))
      (node (ref "SV9") (pin "12") (pinfunction "12_12") (pintype "passive"))
    )
    (net (code "242") (name "VMA") (class "Default")
      (node (ref "IC17") (pin "5") (pinfunction "VMA_5") (pintype "output"))
      (node (ref "IC18") (pin "9") (pinfunction "I0_9") (pintype "input"))
    )
    (net (code "243") (name "unconnected-(IC17A-BA-Pad7)") (class "Default")
      (node (ref "IC17") (pin "7") (pinfunction "BA_7") (pintype "output"))
    )
    (net (code "244") (name "unconnected-(IC19A-Y0-Pad15)") (class "Default")
      (node (ref "IC19") (pin "15") (pinfunction "Y0_15") (pintype "output"))
    )
    (net (code "245") (name "unconnected-(IC19A-Y1-Pad14)") (class "Default")
      (node (ref "IC19") (pin "14") (pinfunction "Y1_14") (pintype "output"))
    )
    (net (code "246") (name "unconnected-(IC19A-Y2-Pad13)") (class "Default")
      (node (ref "IC19") (pin "13") (pinfunction "Y2_13") (pintype "output"))
    )
    (net (code "247") (name "unconnected-(IC19A-Y3-Pad12)") (class "Default")
      (node (ref "IC19") (pin "12") (pinfunction "Y3_12") (pintype "output"))
    )
    (net (code "248") (name "unconnected-(IC19A-Y4-Pad11)") (class "Default")
      (node (ref "IC19") (pin "11") (pinfunction "Y4_11") (pintype "output"))
    )
    (net (code "249") (name "unconnected-(IC19A-Y5-Pad10)") (class "Default")
      (node (ref "IC19") (pin "10") (pinfunction "Y5_10") (pintype "output"))
    )
    (net (code "250") (name "unconnected-(IC20A-R2OUT-Pad9)") (class "Default")
      (node (ref "IC20") (pin "9") (pinfunction "R2OUT_9") (pintype "output"))
    )
    (net (code "251") (name "unconnected-(IC22-NC-Pad1)") (class "Default")
      (node (ref "IC22") (pin "1") (pinfunction "NC_1") (pintype "no_connect"))
    )
    (net (code "252") (name "unconnected-(IC28A-Y1-Pad5)") (class "Default")
      (node (ref "IC28") (pin "5") (pinfunction "Y1_5") (pintype "output"))
    )
    (net (code "253") (name "unconnected-(IC28B-Y0-Pad12)") (class "Default")
      (node (ref "IC28") (pin "12") (pinfunction "Y0_12") (pintype "output"))
    )
    (net (code "254") (name "unconnected-(IC28B-Y1-Pad11)") (class "Default")
      (node (ref "IC28") (pin "11") (pinfunction "Y1_11") (pintype "output"))
    )
    (net (code "255") (name "unconnected-(IC28B-Y2-Pad10)") (class "Default")
      (node (ref "IC28") (pin "10") (pinfunction "Y2_10") (pintype "output"))
    )
    (net (code "256") (name "unconnected-(IC28B-Y3-Pad9)") (class "Default")
      (node (ref "IC28") (pin "9") (pinfunction "Y3_9") (pintype "output"))
    )
    (net (code "257") (name "unconnected-(X1-Pad1)") (class "Default")
      (node (ref "X1") (pin "1") (pinfunction "1_1") (pintype "passive"))
    )
    (net (code "258") (name "unconnected-(X1-Pad9)") (class "Default")
      (node (ref "X1") (pin "9") (pinfunction "9_9") (pintype "passive"))
    )
    (net (code "259") (name "~{89AB}") (class "Default")
      (node (ref "IC22") (pin "20") (pinfunction "~{CS1}_20") (pintype "input"))
      (node (ref "IC22") (pin "22") (pinfunction "~{OE}_22") (pintype "input"))
      (node (ref "IC28") (pin "6") (pinfunction "Y2_6") (pintype "output"))
    )
    (net (code "260") (name "~{CDEF}") (class "Default")
      (node (ref "IC23") (pin "20") (pinfunction "~{CE}_20") (pintype "input"))
      (node (ref "IC23") (pin "22") (pinfunction "~{OE}_22") (pintype "input"))
      (node (ref "IC28") (pin "7") (pinfunction "Y3_7") (pintype "output"))
    )
    (net (code "261") (name "~{HLT}") (class "Default")
      (node (ref "IC17") (pin "2") (pinfunction "HALT_2") (pintype "input"))
      (node (ref "R5") (pin "1") (pinfunction "1_1") (pintype "passive"))
    )
    (net (code "262") (name "~{IO-E}") (class "Default")
      (node (ref "IC19") (pin "9") (pinfunction "Y6_9") (pintype "output"))
      (node (ref "IC24") (pin "23") (pinfunction "CS2_23") (pintype "input"))
    )
    (net (code "263") (name "~{IO-F}") (class "Default")
      (node (ref "IC19") (pin "7") (pinfunction "Y7_7") (pintype "output"))
      (node (ref "IC21") (pin "9") (pinfunction "CS2_9") (pintype "input"))
    )
    (net (code "264") (name "~{IRQ}") (class "Default")
      (node (ref "IC17") (pin "4") (pinfunction "IRQ_4") (pintype "input"))
      (node (ref "IC24") (pin "37") (pinfunction "IRQB_37") (pintype "open_collector"))
      (node (ref "IC24") (pin "38") (pinfunction "IRQA_38") (pintype "open_collector"))
      (node (ref "R7") (pin "1") (pinfunction "1_1") (pintype "passive"))
    )
    (net (code "265") (name "~{NMI}") (class "Default")
      (node (ref "IC17") (pin "6") (pinfunction "NMI_6") (pintype "input"))
      (node (ref "IC21") (pin "7") (pinfunction "IRQ_7") (pintype "output"))
      (node (ref "R6") (pin "1") (pinfunction "1_1") (pintype "passive"))
    )
    (net (code "266") (name "~{RST}") (class "Default")
      (node (ref "IC17") (pin "40") (pinfunction "RESET_40") (pintype "input"))
      (node (ref "IC18") (pin "6") (pinfunction "O_6") (pintype "output"))
      (node (ref "IC24") (pin "34") (pinfunction "RESET_34") (pintype "input"))
    )
  )
)
